# robot_board.net
KiCad netlist of a schematic drawn in EAGLE
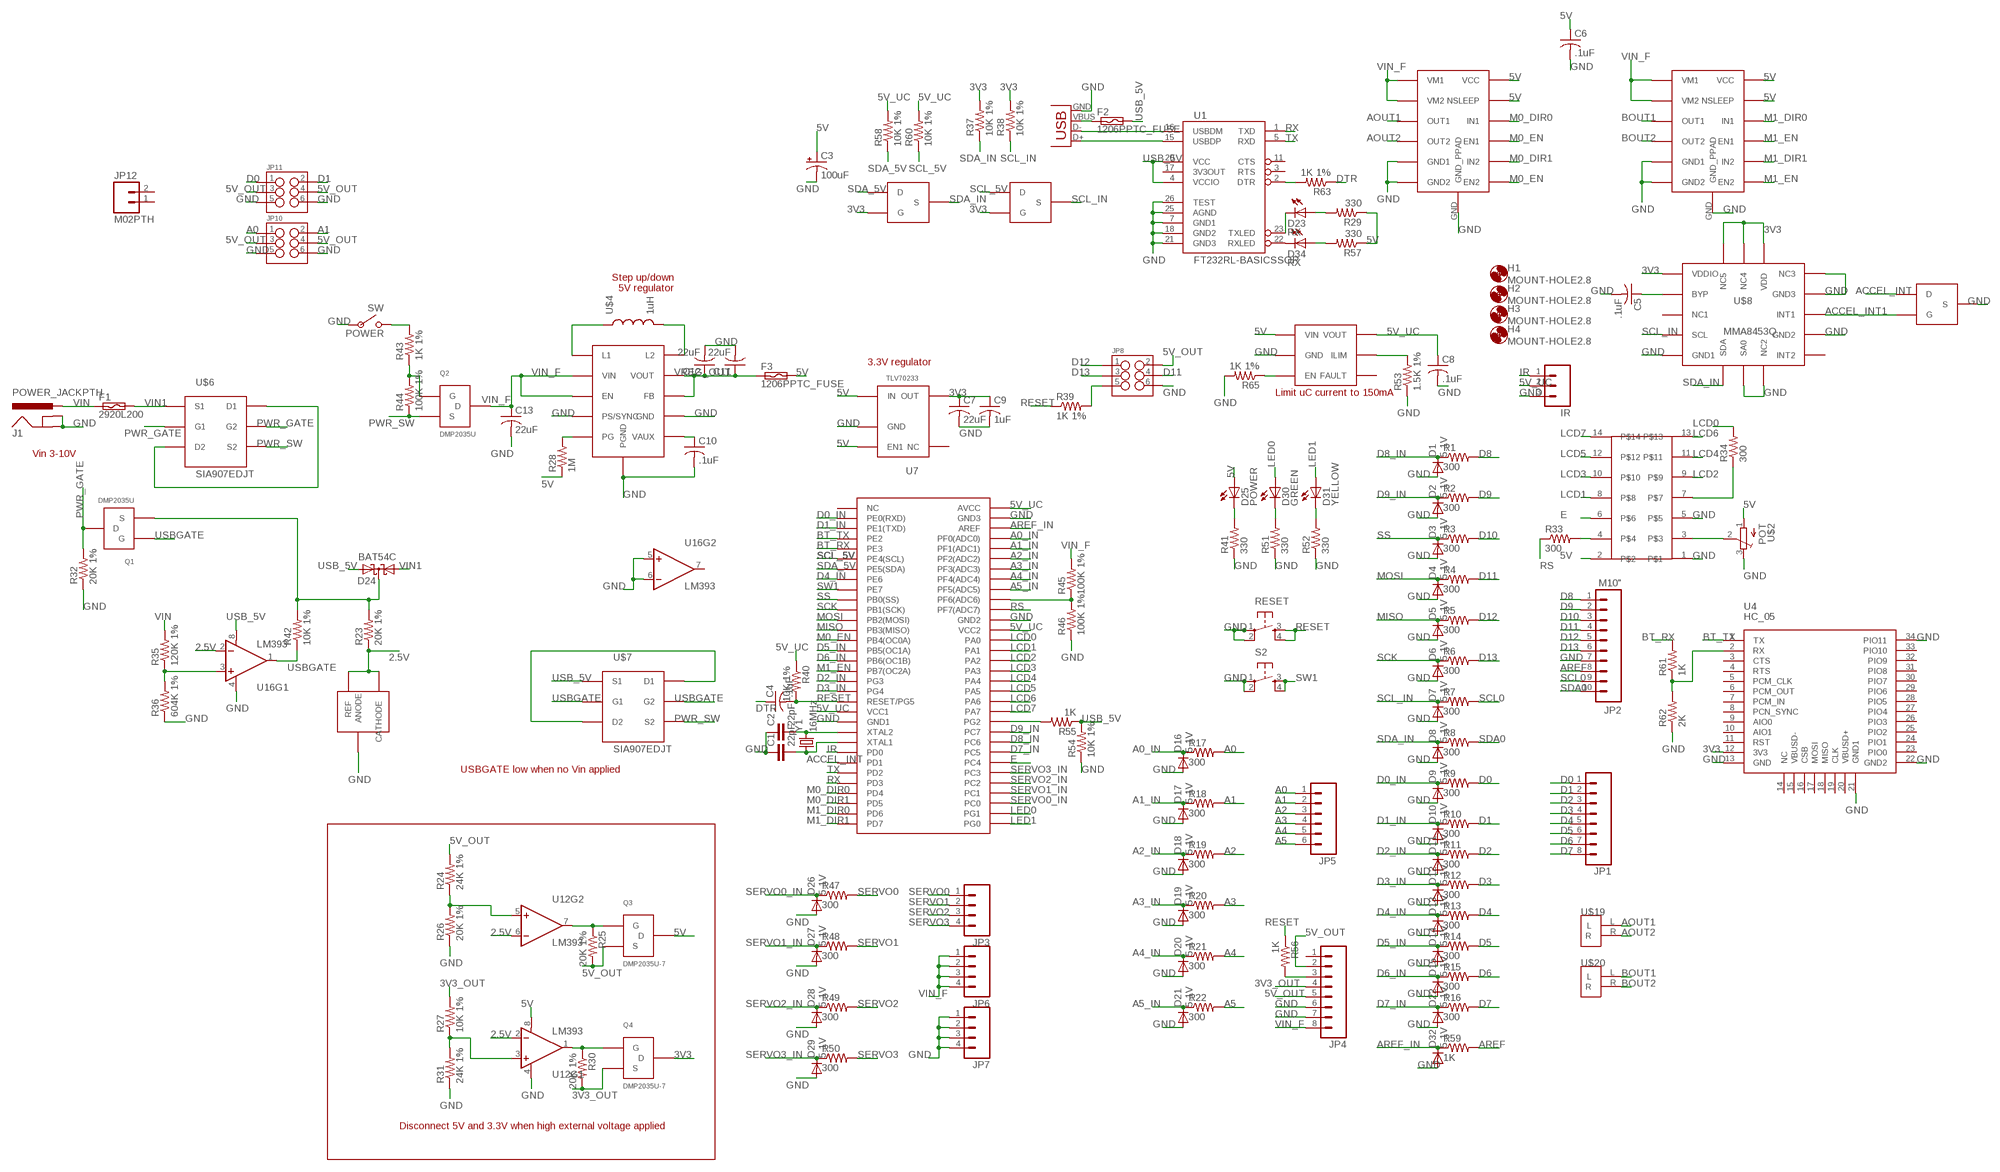
[diagram p0: schematic, sheet 1]

(export (version "E")
  (design (tool "Eeschema 10.0.6"))
  (components
    (comp (ref "C1")
      (value "22pF")
      (footprint "eagle-import:0805")
      (libsource (lib "eagle-import") (part "CAP0805"))
    )
    (comp (ref "C2")
      (value "22pF")
      (footprint "eagle-import:0805")
      (libsource (lib "eagle-import") (part "CAP0805"))
    )
    (comp (ref "C3")
      (value "100uF")
      (footprint "eagle-import:PANASONIC_D")
      (libsource (lib "eagle-import") (part "CAP_POLD"))
    )
    (comp (ref "C4")
      (value ".1uF")
      (footprint "eagle-import:C1206")
      (libsource (lib "eagle-import") (part "C-USC1206"))
    )
    (comp (ref "C5")
      (value ".1uF")
      (footprint "eagle-import:C1206")
      (libsource (lib "eagle-import") (part "C-USC1206"))
    )
    (comp (ref "C6")
      (value ".1uF")
      (footprint "eagle-import:C1206")
      (libsource (lib "eagle-import") (part "C-USC1206"))
    )
    (comp (ref "C7")
      (value "22uF")
      (footprint "eagle-import:C1206")
      (libsource (lib "eagle-import") (part "C-USC1206"))
    )
    (comp (ref "C8")
      (value ".1uF")
      (footprint "eagle-import:C1206")
      (libsource (lib "eagle-import") (part "C-USC1206"))
    )
    (comp (ref "C9")
      (value "1uF")
      (footprint "eagle-import:C1206")
      (libsource (lib "eagle-import") (part "C-USC1206"))
    )
    (comp (ref "C10")
      (value ".1uF")
      (footprint "eagle-import:C1206")
      (libsource (lib "eagle-import") (part "C-USC1206"))
    )
    (comp (ref "C11")
      (value "22uF")
      (footprint "eagle-import:C1206")
      (libsource (lib "eagle-import") (part "C-USC1206"))
    )
    (comp (ref "C12")
      (value "22uF")
      (footprint "eagle-import:C1206")
      (libsource (lib "eagle-import") (part "C-USC1206"))
    )
    (comp (ref "C13")
      (value "22uF")
      (footprint "eagle-import:C1206")
      (libsource (lib "eagle-import") (part "C-USC1206"))
    )
    (comp (ref "D1")
      (value "5.1V")
      (footprint "eagle-import:SOT23-3")
      (libsource (lib "eagle-import") (part "DIODESOT23"))
    )
    (comp (ref "D2")
      (value "5.1V")
      (footprint "eagle-import:SOT23-3")
      (libsource (lib "eagle-import") (part "DIODESOT23"))
    )
    (comp (ref "D3")
      (value "5.1V")
      (footprint "eagle-import:SOT23-3")
      (libsource (lib "eagle-import") (part "DIODESOT23"))
    )
    (comp (ref "D4")
      (value "5.1V")
      (footprint "eagle-import:SOT23-3")
      (libsource (lib "eagle-import") (part "DIODESOT23"))
    )
    (comp (ref "D5")
      (value "5.1V")
      (footprint "eagle-import:SOT23-3")
      (libsource (lib "eagle-import") (part "DIODESOT23"))
    )
    (comp (ref "D6")
      (value "5.1V")
      (footprint "eagle-import:SOT23-3")
      (libsource (lib "eagle-import") (part "DIODESOT23"))
    )
    (comp (ref "D7")
      (value "5.1V")
      (footprint "eagle-import:SOT23-3")
      (libsource (lib "eagle-import") (part "DIODESOT23"))
    )
    (comp (ref "D8")
      (value "5.1V")
      (footprint "eagle-import:SOT23-3")
      (libsource (lib "eagle-import") (part "DIODESOT23"))
    )
    (comp (ref "D9")
      (value "5.1V")
      (footprint "eagle-import:SOT23-3")
      (libsource (lib "eagle-import") (part "DIODESOT23"))
    )
    (comp (ref "D10")
      (value "5.1V")
      (footprint "eagle-import:SOT23-3")
      (libsource (lib "eagle-import") (part "DIODESOT23"))
    )
    (comp (ref "D11")
      (value "5.1V")
      (footprint "eagle-import:SOT23-3")
      (libsource (lib "eagle-import") (part "DIODESOT23"))
    )
    (comp (ref "D12")
      (value "5.1V")
      (footprint "eagle-import:SOT23-3")
      (libsource (lib "eagle-import") (part "DIODESOT23"))
    )
    (comp (ref "D13")
      (value "5.1V")
      (footprint "eagle-import:SOT23-3")
      (libsource (lib "eagle-import") (part "DIODESOT23"))
    )
    (comp (ref "D14")
      (value "5.1V")
      (footprint "eagle-import:SOT23-3")
      (libsource (lib "eagle-import") (part "DIODESOT23"))
    )
    (comp (ref "D15")
      (value "5.1V")
      (footprint "eagle-import:SOT23-3")
      (libsource (lib "eagle-import") (part "DIODESOT23"))
    )
    (comp (ref "D16")
      (value "5.1V")
      (footprint "eagle-import:SOT23-3")
      (libsource (lib "eagle-import") (part "DIODESOT23"))
    )
    (comp (ref "D17")
      (value "5.1V")
      (footprint "eagle-import:SOT23-3")
      (libsource (lib "eagle-import") (part "DIODESOT23"))
    )
    (comp (ref "D18")
      (value "5.1V")
      (footprint "eagle-import:SOT23-3")
      (libsource (lib "eagle-import") (part "DIODESOT23"))
    )
    (comp (ref "D19")
      (value "5.1V")
      (footprint "eagle-import:SOT23-3")
      (libsource (lib "eagle-import") (part "DIODESOT23"))
    )
    (comp (ref "D20")
      (value "5.1V")
      (footprint "eagle-import:SOT23-3")
      (libsource (lib "eagle-import") (part "DIODESOT23"))
    )
    (comp (ref "D21")
      (value "5.1V")
      (footprint "eagle-import:SOT23-3")
      (libsource (lib "eagle-import") (part "DIODESOT23"))
    )
    (comp (ref "D22")
      (value "5.1V")
      (footprint "eagle-import:SOT23-3")
      (libsource (lib "eagle-import") (part "DIODESOT23"))
    )
    (comp (ref "D23")
      (value "RX")
      (footprint "eagle-import:LED-1206")
      (libsource (lib "eagle-import") (part "LED-GREENLILYPAD"))
    )
    (comp (ref "D24")
      (value "BAT54C")
      (footprint "eagle-import:SOT23")
      (libsource (lib "eagle-import") (part "BAT54C"))
    )
    (comp (ref "D25")
      (value "POWER")
      (footprint "eagle-import:LED-1206")
      (libsource (lib "eagle-import") (part "LED-GREENLILYPAD"))
    )
    (comp (ref "D26")
      (value "5.1V")
      (footprint "eagle-import:SOT23-3")
      (libsource (lib "eagle-import") (part "DIODESOT23"))
    )
    (comp (ref "D27")
      (value "5.1V")
      (footprint "eagle-import:SOT23-3")
      (libsource (lib "eagle-import") (part "DIODESOT23"))
    )
    (comp (ref "D28")
      (value "5.1V")
      (footprint "eagle-import:SOT23-3")
      (libsource (lib "eagle-import") (part "DIODESOT23"))
    )
    (comp (ref "D29")
      (value "5.1V")
      (footprint "eagle-import:SOT23-3")
      (libsource (lib "eagle-import") (part "DIODESOT23"))
    )
    (comp (ref "D30")
      (value "GREEN")
      (footprint "eagle-import:LED-1206")
      (libsource (lib "eagle-import") (part "LED-GREENLILYPAD"))
    )
    (comp (ref "D31")
      (value "YELLOW")
      (footprint "eagle-import:LED-1206")
      (libsource (lib "eagle-import") (part "LED-GREENLILYPAD"))
    )
    (comp (ref "D32")
      (value "5.1V")
      (footprint "eagle-import:SOT23-3")
      (libsource (lib "eagle-import") (part "DIODESOT23"))
    )
    (comp (ref "D34")
      (value "RX")
      (footprint "eagle-import:LED-1206")
      (libsource (lib "eagle-import") (part "LED-GREENLILYPAD"))
    )
    (comp (ref "F1")
      (value "2920L200")
      (footprint "eagle-import:SMD050F")
      (libsource (lib "eagle-import") (part "2920L200"))
    )
    (comp (ref "F2")
      (value "1206PPTC_FUSE")
      (footprint "eagle-import:R1206")
      (libsource (lib "eagle-import") (part "1206PPTC_FUSE"))
    )
    (comp (ref "F3")
      (value "1206PPTC_FUSE")
      (footprint "eagle-import:R1206")
      (libsource (lib "eagle-import") (part "1206PPTC_FUSE"))
    )
    (comp (ref "H1")
      (value "MOUNT-HOLE2.8")
      (footprint "eagle-import:2,8")
      (libsource (lib "eagle-import") (part "MOUNT-HOLE2.8"))
    )
    (comp (ref "H2")
      (value "MOUNT-HOLE2.8")
      (footprint "eagle-import:2,8")
      (libsource (lib "eagle-import") (part "MOUNT-HOLE2.8"))
    )
    (comp (ref "H3")
      (value "MOUNT-HOLE2.8")
      (footprint "eagle-import:2,8")
      (libsource (lib "eagle-import") (part "MOUNT-HOLE2.8"))
    )
    (comp (ref "H4")
      (value "MOUNT-HOLE2.8")
      (footprint "eagle-import:2,8")
      (libsource (lib "eagle-import") (part "MOUNT-HOLE2.8"))
    )
    (comp (ref "IR")
      (value "M03PTH")
      (footprint "eagle-import:1X03")
      (libsource (lib "eagle-import") (part "M03PTH"))
    )
    (comp (ref "J1")
      (value "POWER_JACKPTH")
      (footprint "eagle-import:POWER_JACK_PTH")
      (libsource (lib "eagle-import") (part "POWER_JACKPTH"))
    )
    (comp (ref "JP1")
      (value "M081X08")
      (footprint "eagle-import:1X08")
      (libsource (lib "eagle-import") (part "M081X08"))
    )
    (comp (ref "JP2")
      (value "M10\"")
      (footprint "eagle-import:1X10")
      (libsource (lib "eagle-import") (part "M10{dblquote}"))
    )
    (comp (ref "JP3")
      (value "M04PTH")
      (footprint "eagle-import:1X04")
      (libsource (lib "eagle-import") (part "M04PTH"))
    )
    (comp (ref "JP4")
      (value "M081X08")
      (footprint "eagle-import:1X08")
      (libsource (lib "eagle-import") (part "M081X08"))
    )
    (comp (ref "JP5")
      (value "M06SIP")
      (footprint "eagle-import:1X06")
      (libsource (lib "eagle-import") (part "M06SIP"))
    )
    (comp (ref "JP6")
      (value "M04PTH")
      (footprint "eagle-import:1X04")
      (libsource (lib "eagle-import") (part "M04PTH"))
    )
    (comp (ref "JP7")
      (value "M04PTH")
      (footprint "eagle-import:1X04")
      (libsource (lib "eagle-import") (part "M04PTH"))
    )
    (comp (ref "JP8")
      (value "M03X22X3_SILK_SM")
      (footprint "eagle-import:2X3")
      (libsource (lib "eagle-import") (part "M03X22X3_SILK_SM"))
    )
    (comp (ref "JP9")
      (value "USB-B")
      (footprint "eagle-import:USB-B-PTH")
      (libsource (lib "eagle-import") (part "USBPTH"))
    )
    (comp (ref "JP10")
      (value "M03X22X3_SILK_SM")
      (footprint "eagle-import:2X3")
      (libsource (lib "eagle-import") (part "M03X22X3_SILK_SM"))
    )
    (comp (ref "JP11")
      (value "M03X22X3_SILK_SM")
      (footprint "eagle-import:2X3")
      (libsource (lib "eagle-import") (part "M03X22X3_SILK_SM"))
    )
    (comp (ref "JP12")
      (value "M02PTH")
      (footprint "eagle-import:1X02")
      (libsource (lib "eagle-import") (part "M02PTH"))
    )
    (comp (ref "POWER")
      (value "SW")
      (footprint "eagle-import:SW")
      (libsource (lib "eagle-import") (part "SW"))
    )
    (comp (ref "Q1")
      (value "DMP2035U")
      (footprint "eagle-import:SOT23")
      (libsource (lib "eagle-import") (part "DMP2035U"))
    )
    (comp (ref "Q2")
      (value "DMP2035U")
      (footprint "eagle-import:SOT23")
      (libsource (lib "eagle-import") (part "DMP2035U"))
    )
    (comp (ref "Q3")
      (value "DMP2035U-7")
      (footprint "eagle-import:SOT23@1")
      (libsource (lib "eagle-import") (part "DMP2035U-7"))
    )
    (comp (ref "Q4")
      (value "DMP2035U-7")
      (footprint "eagle-import:SOT23@1")
      (libsource (lib "eagle-import") (part "DMP2035U-7"))
    )
    (comp (ref "R1")
      (value "300")
      (footprint "eagle-import:R1206")
      (libsource (lib "eagle-import") (part "R-US_R1206"))
    )
    (comp (ref "R2")
      (value "300")
      (footprint "eagle-import:R1206")
      (libsource (lib "eagle-import") (part "R-US_R1206"))
    )
    (comp (ref "R3")
      (value "300")
      (footprint "eagle-import:R1206")
      (libsource (lib "eagle-import") (part "R-US_R1206"))
    )
    (comp (ref "R4")
      (value "300")
      (footprint "eagle-import:R1206")
      (libsource (lib "eagle-import") (part "R-US_R1206"))
    )
    (comp (ref "R5")
      (value "300")
      (footprint "eagle-import:R1206")
      (libsource (lib "eagle-import") (part "R-US_R1206"))
    )
    (comp (ref "R6")
      (value "300")
      (footprint "eagle-import:R1206")
      (libsource (lib "eagle-import") (part "R-US_R1206"))
    )
    (comp (ref "R7")
      (value "300")
      (footprint "eagle-import:R1206")
      (libsource (lib "eagle-import") (part "R-US_R1206"))
    )
    (comp (ref "R8")
      (value "300")
      (footprint "eagle-import:R1206")
      (libsource (lib "eagle-import") (part "R-US_R1206"))
    )
    (comp (ref "R9")
      (value "300")
      (footprint "eagle-import:R1206")
      (libsource (lib "eagle-import") (part "R-US_R1206"))
    )
    (comp (ref "R10")
      (value "300")
      (footprint "eagle-import:R1206")
      (libsource (lib "eagle-import") (part "R-US_R1206"))
    )
    (comp (ref "R11")
      (value "300")
      (footprint "eagle-import:R1206")
      (libsource (lib "eagle-import") (part "R-US_R1206"))
    )
    (comp (ref "R12")
      (value "300")
      (footprint "eagle-import:R1206")
      (libsource (lib "eagle-import") (part "R-US_R1206"))
    )
    (comp (ref "R13")
      (value "300")
      (footprint "eagle-import:R1206")
      (libsource (lib "eagle-import") (part "R-US_R1206"))
    )
    (comp (ref "R14")
      (value "300")
      (footprint "eagle-import:R1206")
      (libsource (lib "eagle-import") (part "R-US_R1206"))
    )
    (comp (ref "R15")
      (value "300")
      (footprint "eagle-import:R1206")
      (libsource (lib "eagle-import") (part "R-US_R1206"))
    )
    (comp (ref "R16")
      (value "300")
      (footprint "eagle-import:R1206")
      (libsource (lib "eagle-import") (part "R-US_R1206"))
    )
    (comp (ref "R17")
      (value "300")
      (footprint "eagle-import:R1206")
      (libsource (lib "eagle-import") (part "R-US_R1206"))
    )
    (comp (ref "R18")
      (value "300")
      (footprint "eagle-import:R1206")
      (libsource (lib "eagle-import") (part "R-US_R1206"))
    )
    (comp (ref "R19")
      (value "300")
      (footprint "eagle-import:R1206")
      (libsource (lib "eagle-import") (part "R-US_R1206"))
    )
    (comp (ref "R20")
      (value "300")
      (footprint "eagle-import:R1206")
      (libsource (lib "eagle-import") (part "R-US_R1206"))
    )
    (comp (ref "R21")
      (value "300")
      (footprint "eagle-import:R1206")
      (libsource (lib "eagle-import") (part "R-US_R1206"))
    )
    (comp (ref "R22")
      (value "300")
      (footprint "eagle-import:R1206")
      (libsource (lib "eagle-import") (part "R-US_R1206"))
    )
    (comp (ref "R23")
      (value "20K 1%")
      (footprint "eagle-import:R1206")
      (libsource (lib "eagle-import") (part "R-US_R1206"))
    )
    (comp (ref "R24")
      (value "24K 1%")
      (footprint "eagle-import:R1206")
      (libsource (lib "eagle-import") (part "R-US_R1206"))
    )
    (comp (ref "R25")
      (value "20K 1%")
      (footprint "eagle-import:R1206")
      (libsource (lib "eagle-import") (part "R-US_R1206"))
    )
    (comp (ref "R26")
      (value "20K 1%")
      (footprint "eagle-import:R1206")
      (libsource (lib "eagle-import") (part "R-US_R1206"))
    )
    (comp (ref "R27")
      (value "10K 1%")
      (footprint "eagle-import:R1206")
      (libsource (lib "eagle-import") (part "R-US_R1206"))
    )
    (comp (ref "R28")
      (value "1M")
      (footprint "eagle-import:R1206")
      (libsource (lib "eagle-import") (part "R-US_R1206"))
    )
    (comp (ref "R29")
      (value "330")
      (footprint "eagle-import:R1206")
      (libsource (lib "eagle-import") (part "R-US_R1206"))
    )
    (comp (ref "R30")
      (value "20K 1%")
      (footprint "eagle-import:R1206")
      (libsource (lib "eagle-import") (part "R-US_R1206"))
    )
    (comp (ref "R31")
      (value "24K 1%")
      (footprint "eagle-import:R1206")
      (libsource (lib "eagle-import") (part "R-US_R1206"))
    )
    (comp (ref "R32")
      (value "20K 1%")
      (footprint "eagle-import:R1206")
      (libsource (lib "eagle-import") (part "R-US_R1206"))
    )
    (comp (ref "R33")
      (value "300")
      (footprint "eagle-import:R1206")
      (libsource (lib "eagle-import") (part "R-US_R1206"))
    )
    (comp (ref "R34")
      (value "300")
      (footprint "eagle-import:R1206")
      (libsource (lib "eagle-import") (part "R-US_R1206"))
    )
    (comp (ref "R35")
      (value "120K 1%")
      (footprint "eagle-import:R1206")
      (libsource (lib "eagle-import") (part "R-US_R1206"))
    )
    (comp (ref "R36")
      (value "604K 1%")
      (footprint "eagle-import:R1206")
      (libsource (lib "eagle-import") (part "R-US_R1206"))
    )
    (comp (ref "R37")
      (value "10K 1%")
      (footprint "eagle-import:R1206")
      (libsource (lib "eagle-import") (part "R-US_R1206"))
    )
    (comp (ref "R38")
      (value "10K 1%")
      (footprint "eagle-import:R1206")
      (libsource (lib "eagle-import") (part "R-US_R1206"))
    )
    (comp (ref "R39")
      (value "1K 1%")
      (footprint "eagle-import:R1206")
      (libsource (lib "eagle-import") (part "R-US_R1206"))
    )
    (comp (ref "R40")
      (value "10K 1%")
      (footprint "eagle-import:R1206")
      (libsource (lib "eagle-import") (part "R-US_R1206"))
    )
    (comp (ref "R41")
      (value "330")
      (footprint "eagle-import:R1206")
      (libsource (lib "eagle-import") (part "R-US_R1206"))
    )
    (comp (ref "R42")
      (value "10K 1%")
      (footprint "eagle-import:R1206")
      (libsource (lib "eagle-import") (part "R-US_R1206"))
    )
    (comp (ref "R43")
      (value "1K 1%")
      (footprint "eagle-import:R1206")
      (libsource (lib "eagle-import") (part "R-US_R1206"))
    )
    (comp (ref "R44")
      (value "100K 1%")
      (footprint "eagle-import:R1206")
      (libsource (lib "eagle-import") (part "R-US_R1206"))
    )
    (comp (ref "R45")
      (value "100K 1%")
      (footprint "eagle-import:R1206")
      (libsource (lib "eagle-import") (part "R-US_R1206"))
    )
    (comp (ref "R46")
      (value "100K 1%")
      (footprint "eagle-import:R1206")
      (libsource (lib "eagle-import") (part "R-US_R1206"))
    )
    (comp (ref "R47")
      (value "300")
      (footprint "eagle-import:R1206")
      (libsource (lib "eagle-import") (part "R-US_R1206"))
    )
    (comp (ref "R48")
      (value "300")
      (footprint "eagle-import:R1206")
      (libsource (lib "eagle-import") (part "R-US_R1206"))
    )
    (comp (ref "R49")
      (value "300")
      (footprint "eagle-import:R1206")
      (libsource (lib "eagle-import") (part "R-US_R1206"))
    )
    (comp (ref "R50")
      (value "300")
      (footprint "eagle-import:R1206")
      (libsource (lib "eagle-import") (part "R-US_R1206"))
    )
    (comp (ref "R51")
      (value "330")
      (footprint "eagle-import:R1206")
      (libsource (lib "eagle-import") (part "R-US_R1206"))
    )
    (comp (ref "R52")
      (value "330")
      (footprint "eagle-import:R1206")
      (libsource (lib "eagle-import") (part "R-US_R1206"))
    )
    (comp (ref "R53")
      (value "1.5K 1%")
      (footprint "eagle-import:R1206")
      (libsource (lib "eagle-import") (part "R-US_R1206"))
    )
    (comp (ref "R54")
      (value "10K 1%")
      (footprint "eagle-import:R1206")
      (libsource (lib "eagle-import") (part "R-US_R1206"))
    )
    (comp (ref "R55")
      (value "1K")
      (footprint "eagle-import:R1206")
      (libsource (lib "eagle-import") (part "R-US_R1206"))
    )
    (comp (ref "R56")
      (value "1K")
      (footprint "eagle-import:R1206")
      (libsource (lib "eagle-import") (part "R-US_R1206"))
    )
    (comp (ref "R57")
      (value "330")
      (footprint "eagle-import:R1206")
      (libsource (lib "eagle-import") (part "R-US_R1206"))
    )
    (comp (ref "R58")
      (value "10K 1%")
      (footprint "eagle-import:R1206")
      (libsource (lib "eagle-import") (part "R-US_R1206"))
    )
    (comp (ref "R59")
      (value "1K")
      (footprint "eagle-import:R1206")
      (libsource (lib "eagle-import") (part "R-US_R1206"))
    )
    (comp (ref "R60")
      (value "10K 1%")
      (footprint "eagle-import:R1206")
      (libsource (lib "eagle-import") (part "R-US_R1206"))
    )
    (comp (ref "R61")
      (value "1K")
      (footprint "eagle-import:R1206")
      (libsource (lib "eagle-import") (part "R-US_R1206"))
    )
    (comp (ref "R62")
      (value "2K")
      (footprint "eagle-import:R1206")
      (libsource (lib "eagle-import") (part "R-US_R1206"))
    )
    (comp (ref "R63")
      (value "1K 1%")
      (footprint "eagle-import:R1206")
      (libsource (lib "eagle-import") (part "R-US_R1206"))
    )
    (comp (ref "R65")
      (value "1K 1%")
      (footprint "eagle-import:R1206")
      (libsource (lib "eagle-import") (part "R-US_R1206"))
    )
    (comp (ref "RESET")
      (value "TAC_SWITCHPTH")
      (footprint "eagle-import:TACTILE-PTH")
      (libsource (lib "eagle-import") (part "TAC_SWITCHPTH"))
    )
    (comp (ref "S2")
      (value "TAC_SWITCHPTH")
      (footprint "eagle-import:TACTILE-PTH")
      (libsource (lib "eagle-import") (part "TAC_SWITCHPTH"))
    )
    (comp (ref "U$1")
      (value "2X7HEADER")
      (footprint "eagle-import:2X7")
      (libsource (lib "eagle-import") (part "2X7HEADER"))
    )
    (comp (ref "U$2")
      (value "POT")
      (footprint "eagle-import:POT")
      (libsource (lib "eagle-import") (part "POT"))
    )
    (comp (ref "U$3")
      (value "TPS63061")
      (footprint "eagle-import:WSON-10")
      (libsource (lib "eagle-import") (part "TPS63061"))
    )
    (comp (ref "U$4")
      (value "1uH")
      (footprint "eagle-import:TAIYO4012")
      (libsource (lib "eagle-import") (part "TAIYO4012"))
    )
    (comp (ref "U$5")
      (value "AP431SAG-7")
      (footprint "eagle-import:SOT23")
      (libsource (lib "eagle-import") (part "AP431SAG-7"))
    )
    (comp (ref "U$6")
      (value "SIA907EDJT")
      (footprint "eagle-import:SC70T")
      (libsource (lib "eagle-import") (part "SIA907EDJT"))
    )
    (comp (ref "U$7")
      (value "SIA907EDJT")
      (footprint "eagle-import:SC70T")
      (libsource (lib "eagle-import") (part "SIA907EDJT"))
    )
    (comp (ref "U$8")
      (value "MMA8453Q")
      (footprint "eagle-import:QFN-COL")
      (libsource (lib "eagle-import") (part "MMA8453Q"))
    )
    (comp (ref "U$9")
      (value "BSS138")
      (footprint "eagle-import:SOT23")
      (libsource (lib "eagle-import") (part "BSS138"))
    )
    (comp (ref "U$10")
      (value "BSS138")
      (footprint "eagle-import:SOT23")
      (libsource (lib "eagle-import") (part "BSS138"))
    )
    (comp (ref "U$11")
      (value "BSS138")
      (footprint "eagle-import:SOT23")
      (libsource (lib "eagle-import") (part "BSS138"))
    )
    (comp (ref "U$19")
      (value "2POS_TERMINAL")
      (footprint "eagle-import:2POS_TERMINAL")
      (libsource (lib "eagle-import") (part "2POS_TERMINAL"))
    )
    (comp (ref "U$20")
      (value "2POS_TERMINAL")
      (footprint "eagle-import:2POS_TERMINAL")
      (libsource (lib "eagle-import") (part "2POS_TERMINAL"))
    )
    (comp (ref "U1")
      (value "FT232RL-BASICSSOP")
      (footprint "eagle-import:SSOP28DB")
      (libsource (lib "eagle-import") (part "FT232RL-BASICSSOP"))
    )
    (comp (ref "U4")
      (value "HC_05")
      (footprint "eagle-import:BLUETOOTH_SMD")
      (libsource (lib "eagle-import") (part "HC_05"))
    )
    (comp (ref "U7")
      (value "TLV70233")
      (footprint "eagle-import:SOT-23-5")
      (libsource (lib "eagle-import") (part "TLV70233"))
    )
    (comp (ref "U8")
      (value "MIC2009A")
      (footprint "eagle-import:SOT23-M5")
      (libsource (lib "eagle-import") (part "MIC2009A"))
    )
    (comp (ref "U9")
      (value "DRV8839")
      (footprint "eagle-import:PWSON-N12")
      (libsource (lib "eagle-import") (part "DRV8839"))
    )
    (comp (ref "U10")
      (value "DRV8839")
      (footprint "eagle-import:PWSON-N12")
      (libsource (lib "eagle-import") (part "DRV8839"))
    )
    (comp (ref "U12")
      (value "LM393")
      (footprint "eagle-import:SO08")
      (libsource (lib "eagle-import") (part "LM393"))
    )
    (comp (ref "U16")
      (value "LM393")
      (footprint "eagle-import:SO08")
      (libsource (lib "eagle-import") (part "LM393"))
    )
    (comp (ref "U17")
      (value "ATMEGA325PA")
      (footprint "eagle-import:TQFP64")
      (libsource (lib "eagle-import") (part "ATMEGA325PA"))
    )
    (comp (ref "Y1")
      (value "16MHz")
      (footprint "eagle-import:CRYSTAL-SMD-10.5X4.8-2PIN")
      (libsource (lib "eagle-import") (part "CRYSTAL10.5X4.8"))
    )
  )
  (nets
    (net (code "1") (name "/2.5V") (class "Default")
      (node (ref "R23") (pin "1") (pinfunction "1_1") (pintype "passive"))
      (node (ref "U$5") (pin "1") (pinfunction "CATHODE_1") (pintype "bidirectional"))
      (node (ref "U$5") (pin "2") (pinfunction "REF_2") (pintype "bidirectional"))
      (node (ref "U12") (pin "2") (pinfunction "-IN_2") (pintype "input"))
      (node (ref "U12") (pin "6") (pinfunction "-IN_6") (pintype "input"))
      (node (ref "U16") (pin "2") (pinfunction "-IN_2") (pintype "input"))
    )
    (net (code "2") (name "/3V3") (class "Default")
      (node (ref "C7") (pin "1") (pinfunction "1_1") (pintype "passive"))
      (node (ref "C9") (pin "1") (pinfunction "1_1") (pintype "passive"))
      (node (ref "Q4") (pin "3") (pinfunction "D_3") (pintype "bidirectional"))
      (node (ref "R37") (pin "2") (pinfunction "2_2") (pintype "passive"))
      (node (ref "R38") (pin "2") (pinfunction "2_2") (pintype "passive"))
      (node (ref "U$10") (pin "1") (pinfunction "G_1") (pintype "bidirectional"))
      (node (ref "U$8") (pin "P$1") (pinfunction "VDDIO_P$1") (pintype "bidirectional"))
      (node (ref "U$8") (pin "P$14") (pinfunction "VDD_P$14") (pintype "bidirectional"))
      (node (ref "U$8") (pin "P$15") (pinfunction "NC4_P$15") (pintype "bidirectional"))
      (node (ref "U$8") (pin "P$16") (pinfunction "NC5_P$16") (pintype "bidirectional"))
      (node (ref "U$9") (pin "1") (pinfunction "G_1") (pintype "bidirectional"))
      (node (ref "U4") (pin "12") (pinfunction "3V3_12") (pintype "bidirectional"))
      (node (ref "U7") (pin "P$4") (pinfunction "OUT_P$4") (pintype "bidirectional"))
    )
    (net (code "3") (name "/3V3_OUT") (class "Default")
      (node (ref "JP4") (pin "4") (pinfunction "4_4") (pintype "passive"))
      (node (ref "Q4") (pin "2") (pinfunction "S_2") (pintype "bidirectional"))
      (node (ref "R27") (pin "2") (pinfunction "2_2") (pintype "passive"))
      (node (ref "R30") (pin "2") (pinfunction "2_2") (pintype "passive"))
    )
    (net (code "4") (name "/5V") (class "Default")
      (node (ref "C3") (pin "+") (pinfunction "+_+") (pintype "passive"))
      (node (ref "C6") (pin "1") (pinfunction "1_1") (pintype "passive"))
      (node (ref "D25") (pin "A") (pinfunction "A_A") (pintype "passive"))
      (node (ref "F3") (pin "2") (pinfunction "2_2") (pintype "passive"))
      (node (ref "Q3") (pin "3") (pinfunction "D_3") (pintype "bidirectional"))
      (node (ref "R28") (pin "1") (pinfunction "1_1") (pintype "passive"))
      (node (ref "R29") (pin "1") (pinfunction "1_1") (pintype "passive"))
      (node (ref "R57") (pin "1") (pinfunction "1_1") (pintype "passive"))
      (node (ref "U$1") (pin "2") (pinfunction "P$2_2") (pintype "bidirectional"))
      (node (ref "U$2") (pin "1") (pinfunction "A_1") (pintype "passive"))
      (node (ref "U10") (pin "P$7") (pinfunction "VCC_P$7") (pintype "bidirectional"))
      (node (ref "U10") (pin "P$8") (pinfunction "NSLEEP_P$8") (pintype "bidirectional"))
      (node (ref "U12") (pin "8") (pinfunction "V+_8") (pintype "power_in"))
      (node (ref "U7") (pin "P$1") (pinfunction "IN_P$1") (pintype "bidirectional"))
      (node (ref "U7") (pin "P$3") (pinfunction "EN1_P$3") (pintype "bidirectional"))
      (node (ref "U8") (pin "P$1") (pinfunction "VIN_P$1") (pintype "bidirectional"))
      (node (ref "U9") (pin "P$7") (pinfunction "VCC_P$7") (pintype "bidirectional"))
      (node (ref "U9") (pin "P$8") (pinfunction "NSLEEP_P$8") (pintype "bidirectional"))
    )
    (net (code "5") (name "/5V_OUT") (class "Default")
      (node (ref "JP10") (pin "3") (pinfunction "3_3") (pintype "bidirectional"))
      (node (ref "JP10") (pin "4") (pinfunction "4_4") (pintype "bidirectional"))
      (node (ref "JP11") (pin "3") (pinfunction "3_3") (pintype "bidirectional"))
      (node (ref "JP11") (pin "4") (pinfunction "4_4") (pintype "bidirectional"))
      (node (ref "JP4") (pin "2") (pinfunction "2_2") (pintype "passive"))
      (node (ref "JP4") (pin "5") (pinfunction "5_5") (pintype "passive"))
      (node (ref "JP8") (pin "2") (pinfunction "2_2") (pintype "bidirectional"))
      (node (ref "Q3") (pin "2") (pinfunction "S_2") (pintype "bidirectional"))
      (node (ref "R24") (pin "2") (pinfunction "2_2") (pintype "passive"))
      (node (ref "R25") (pin "2") (pinfunction "2_2") (pintype "passive"))
    )
    (net (code "6") (name "/5V_UC") (class "Default")
      (node (ref "C8") (pin "1") (pinfunction "1_1") (pintype "passive"))
      (node (ref "IR") (pin "2") (pinfunction "2_2") (pintype "passive"))
      (node (ref "R40") (pin "1") (pinfunction "1_1") (pintype "passive"))
      (node (ref "R58") (pin "2") (pinfunction "2_2") (pintype "passive"))
      (node (ref "R60") (pin "2") (pinfunction "2_2") (pintype "passive"))
      (node (ref "U17") (pin "21") (pinfunction "VCC1_21") (pintype "bidirectional"))
      (node (ref "U17") (pin "52") (pinfunction "VCC2_52") (pintype "bidirectional"))
      (node (ref "U17") (pin "64") (pinfunction "AVCC_64") (pintype "bidirectional"))
      (node (ref "U8") (pin "P$6") (pinfunction "VOUT_P$6") (pintype "bidirectional"))
    )
    (net (code "7") (name "/A0") (class "Default")
      (node (ref "JP10") (pin "1") (pinfunction "1_1") (pintype "bidirectional"))
      (node (ref "JP5") (pin "1") (pinfunction "1_1") (pintype "passive"))
      (node (ref "R17") (pin "2") (pinfunction "2_2") (pintype "passive"))
    )
    (net (code "8") (name "/A0_IN") (class "Default")
      (node (ref "D16") (pin "3") (pinfunction "C_3") (pintype "passive"))
      (node (ref "R17") (pin "1") (pinfunction "1_1") (pintype "passive"))
      (node (ref "U17") (pin "61") (pinfunction "PF0(ADC0)_61") (pintype "bidirectional"))
    )
    (net (code "9") (name "/A1") (class "Default")
      (node (ref "JP10") (pin "2") (pinfunction "2_2") (pintype "bidirectional"))
      (node (ref "JP5") (pin "2") (pinfunction "2_2") (pintype "passive"))
      (node (ref "R18") (pin "2") (pinfunction "2_2") (pintype "passive"))
    )
    (net (code "10") (name "/A1_IN") (class "Default")
      (node (ref "D17") (pin "3") (pinfunction "C_3") (pintype "passive"))
      (node (ref "R18") (pin "1") (pinfunction "1_1") (pintype "passive"))
      (node (ref "U17") (pin "60") (pinfunction "PF1(ADC1)_60") (pintype "bidirectional"))
    )
    (net (code "11") (name "/A2") (class "Default")
      (node (ref "JP5") (pin "3") (pinfunction "3_3") (pintype "passive"))
      (node (ref "R19") (pin "2") (pinfunction "2_2") (pintype "passive"))
    )
    (net (code "12") (name "/A2_IN") (class "Default")
      (node (ref "D18") (pin "3") (pinfunction "C_3") (pintype "passive"))
      (node (ref "R19") (pin "1") (pinfunction "1_1") (pintype "passive"))
      (node (ref "U17") (pin "59") (pinfunction "PF2(ADC2)_59") (pintype "bidirectional"))
    )
    (net (code "13") (name "/A3") (class "Default")
      (node (ref "JP5") (pin "4") (pinfunction "4_4") (pintype "passive"))
      (node (ref "R20") (pin "2") (pinfunction "2_2") (pintype "passive"))
    )
    (net (code "14") (name "/A3_IN") (class "Default")
      (node (ref "D19") (pin "3") (pinfunction "C_3") (pintype "passive"))
      (node (ref "R20") (pin "1") (pinfunction "1_1") (pintype "passive"))
      (node (ref "U17") (pin "58") (pinfunction "PF3(ADC3)_58") (pintype "bidirectional"))
    )
    (net (code "15") (name "/A4") (class "Default")
      (node (ref "JP5") (pin "5") (pinfunction "5_5") (pintype "passive"))
      (node (ref "R21") (pin "2") (pinfunction "2_2") (pintype "passive"))
    )
    (net (code "16") (name "/A4_IN") (class "Default")
      (node (ref "D20") (pin "3") (pinfunction "C_3") (pintype "passive"))
      (node (ref "R21") (pin "1") (pinfunction "1_1") (pintype "passive"))
      (node (ref "U17") (pin "57") (pinfunction "PF4(ADC4)_57") (pintype "bidirectional"))
    )
    (net (code "17") (name "/A5") (class "Default")
      (node (ref "JP5") (pin "6") (pinfunction "6_6") (pintype "passive"))
      (node (ref "R22") (pin "2") (pinfunction "2_2") (pintype "passive"))
    )
    (net (code "18") (name "/A5_IN") (class "Default")
      (node (ref "D21") (pin "3") (pinfunction "C_3") (pintype "passive"))
      (node (ref "R22") (pin "1") (pinfunction "1_1") (pintype "passive"))
      (node (ref "U17") (pin "56") (pinfunction "PF5(ADC5)_56") (pintype "bidirectional"))
    )
    (net (code "19") (name "/ACCEL_INT") (class "Default")
      (node (ref "U$11") (pin "3") (pinfunction "D_3") (pintype "bidirectional"))
      (node (ref "U17") (pin "26") (pinfunction "PD1_26") (pintype "bidirectional"))
    )
    (net (code "20") (name "/ACCEL_INT1") (class "Default")
      (node (ref "U$11") (pin "1") (pinfunction "G_1") (pintype "bidirectional"))
      (node (ref "U$8") (pin "P$11") (pinfunction "INT1_P$11") (pintype "bidirectional"))
    )
    (net (code "21") (name "/AOUT1") (class "Default")
      (node (ref "U$19") (pin "L") (pinfunction "L_L") (pintype "bidirectional"))
      (node (ref "U9") (pin "P$3") (pinfunction "OUT1_P$3") (pintype "bidirectional"))
    )
    (net (code "22") (name "/AOUT2") (class "Default")
      (node (ref "U$19") (pin "R") (pinfunction "R_R") (pintype "bidirectional"))
      (node (ref "U9") (pin "P$4") (pinfunction "OUT2_P$4") (pintype "bidirectional"))
    )
    (net (code "23") (name "/AREF") (class "Default")
      (node (ref "JP2") (pin "8") (pinfunction "8_8") (pintype "passive"))
      (node (ref "R59") (pin "2") (pinfunction "2_2") (pintype "passive"))
    )
    (net (code "24") (name "/AREF_IN") (class "Default")
      (node (ref "D32") (pin "3") (pinfunction "C_3") (pintype "passive"))
      (node (ref "R59") (pin "1") (pinfunction "1_1") (pintype "passive"))
      (node (ref "U17") (pin "62") (pinfunction "AREF_62") (pintype "bidirectional"))
    )
    (net (code "25") (name "/BOUT1") (class "Default")
      (node (ref "U$20") (pin "L") (pinfunction "L_L") (pintype "bidirectional"))
      (node (ref "U10") (pin "P$3") (pinfunction "OUT1_P$3") (pintype "bidirectional"))
    )
    (net (code "26") (name "/BOUT2") (class "Default")
      (node (ref "U$20") (pin "R") (pinfunction "R_R") (pintype "bidirectional"))
      (node (ref "U10") (pin "P$4") (pinfunction "OUT2_P$4") (pintype "bidirectional"))
    )
    (net (code "27") (name "/BT_RX") (class "Default")
      (node (ref "R61") (pin "2") (pinfunction "2_2") (pintype "passive"))
      (node (ref "U17") (pin "5") (pinfunction "PE3_5") (pintype "bidirectional"))
    )
    (net (code "28") (name "/BT_TX") (class "Default")
      (node (ref "U17") (pin "4") (pinfunction "PE2_4") (pintype "bidirectional"))
      (node (ref "U4") (pin "1") (pinfunction "TX_1") (pintype "bidirectional"))
    )
    (net (code "29") (name "/D0") (class "Default")
      (node (ref "JP1") (pin "1") (pinfunction "1_1") (pintype "passive"))
      (node (ref "JP11") (pin "1") (pinfunction "1_1") (pintype "bidirectional"))
      (node (ref "R9") (pin "2") (pinfunction "2_2") (pintype "passive"))
    )
    (net (code "30") (name "/D0_IN") (class "Default")
      (node (ref "D9") (pin "3") (pinfunction "C_3") (pintype "passive"))
      (node (ref "R9") (pin "1") (pinfunction "1_1") (pintype "passive"))
      (node (ref "U17") (pin "2") (pinfunction "PE0(RXD)_2") (pintype "bidirectional"))
    )
    (net (code "31") (name "/D1") (class "Default")
      (node (ref "JP1") (pin "2") (pinfunction "2_2") (pintype "passive"))
      (node (ref "JP11") (pin "2") (pinfunction "2_2") (pintype "bidirectional"))
      (node (ref "R10") (pin "2") (pinfunction "2_2") (pintype "passive"))
    )
    (net (code "32") (name "/D1_IN") (class "Default")
      (node (ref "D10") (pin "3") (pinfunction "C_3") (pintype "passive"))
      (node (ref "R10") (pin "1") (pinfunction "1_1") (pintype "passive"))
      (node (ref "U17") (pin "3") (pinfunction "PE1(TXD)_3") (pintype "bidirectional"))
    )
    (net (code "33") (name "/D2") (class "Default")
      (node (ref "JP1") (pin "3") (pinfunction "3_3") (pintype "passive"))
      (node (ref "R11") (pin "2") (pinfunction "2_2") (pintype "passive"))
    )
    (net (code "34") (name "/D2_IN") (class "Default")
      (node (ref "D11") (pin "3") (pinfunction "C_3") (pintype "passive"))
      (node (ref "R11") (pin "1") (pinfunction "1_1") (pintype "passive"))
      (node (ref "U17") (pin "18") (pinfunction "PG3_18") (pintype "bidirectional"))
    )
    (net (code "35") (name "/D3") (class "Default")
      (node (ref "JP1") (pin "4") (pinfunction "4_4") (pintype "passive"))
      (node (ref "R12") (pin "2") (pinfunction "2_2") (pintype "passive"))
    )
    (net (code "36") (name "/D3_IN") (class "Default")
      (node (ref "D12") (pin "3") (pinfunction "C_3") (pintype "passive"))
      (node (ref "R12") (pin "1") (pinfunction "1_1") (pintype "passive"))
      (node (ref "U17") (pin "19") (pinfunction "PG4_19") (pintype "bidirectional"))
    )
    (net (code "37") (name "/D4") (class "Default")
      (node (ref "JP1") (pin "5") (pinfunction "5_5") (pintype "passive"))
      (node (ref "R13") (pin "2") (pinfunction "2_2") (pintype "passive"))
    )
    (net (code "38") (name "/D4_IN") (class "Default")
      (node (ref "D13") (pin "3") (pinfunction "C_3") (pintype "passive"))
      (node (ref "R13") (pin "1") (pinfunction "1_1") (pintype "passive"))
      (node (ref "U17") (pin "8") (pinfunction "PE6_8") (pintype "bidirectional"))
    )
    (net (code "39") (name "/D5") (class "Default")
      (node (ref "JP1") (pin "6") (pinfunction "6_6") (pintype "passive"))
      (node (ref "R14") (pin "2") (pinfunction "2_2") (pintype "passive"))
    )
    (net (code "40") (name "/D5_IN") (class "Default")
      (node (ref "D14") (pin "3") (pinfunction "C_3") (pintype "passive"))
      (node (ref "R14") (pin "1") (pinfunction "1_1") (pintype "passive"))
      (node (ref "U17") (pin "15") (pinfunction "PB5(OC1A)_15") (pintype "bidirectional"))
    )
    (net (code "41") (name "/D6") (class "Default")
      (node (ref "JP1") (pin "7") (pinfunction "7_7") (pintype "passive"))
      (node (ref "R15") (pin "2") (pinfunction "2_2") (pintype "passive"))
    )
    (net (code "42") (name "/D6_IN") (class "Default")
      (node (ref "D15") (pin "3") (pinfunction "C_3") (pintype "passive"))
      (node (ref "R15") (pin "1") (pinfunction "1_1") (pintype "passive"))
      (node (ref "U17") (pin "16") (pinfunction "PB6(OC1B)_16") (pintype "bidirectional"))
    )
    (net (code "43") (name "/D7") (class "Default")
      (node (ref "JP1") (pin "8") (pinfunction "8_8") (pintype "passive"))
      (node (ref "R16") (pin "2") (pinfunction "2_2") (pintype "passive"))
    )
    (net (code "44") (name "/D7_IN") (class "Default")
      (node (ref "D22") (pin "3") (pinfunction "C_3") (pintype "passive"))
      (node (ref "R16") (pin "1") (pinfunction "1_1") (pintype "passive"))
      (node (ref "U17") (pin "40") (pinfunction "PC5_40") (pintype "bidirectional"))
    )
    (net (code "45") (name "/D8") (class "Default")
      (node (ref "JP2") (pin "1") (pinfunction "1_1") (pintype "passive"))
      (node (ref "R1") (pin "2") (pinfunction "2_2") (pintype "passive"))
    )
    (net (code "46") (name "/D8_IN") (class "Default")
      (node (ref "D1") (pin "3") (pinfunction "C_3") (pintype "passive"))
      (node (ref "R1") (pin "1") (pinfunction "1_1") (pintype "passive"))
      (node (ref "U17") (pin "41") (pinfunction "PC6_41") (pintype "bidirectional"))
    )
    (net (code "47") (name "/D9") (class "Default")
      (node (ref "JP2") (pin "2") (pinfunction "2_2") (pintype "passive"))
      (node (ref "R2") (pin "2") (pinfunction "2_2") (pintype "passive"))
    )
    (net (code "48") (name "/D9_IN") (class "Default")
      (node (ref "D2") (pin "3") (pinfunction "C_3") (pintype "passive"))
      (node (ref "R2") (pin "1") (pinfunction "1_1") (pintype "passive"))
      (node (ref "U17") (pin "42") (pinfunction "PC7_42") (pintype "bidirectional"))
    )
    (net (code "49") (name "/D10") (class "Default")
      (node (ref "JP2") (pin "3") (pinfunction "3_3") (pintype "passive"))
      (node (ref "R3") (pin "2") (pinfunction "2_2") (pintype "passive"))
    )
    (net (code "50") (name "/D11") (class "Default")
      (node (ref "JP2") (pin "4") (pinfunction "4_4") (pintype "passive"))
      (node (ref "JP8") (pin "4") (pinfunction "4_4") (pintype "bidirectional"))
      (node (ref "R4") (pin "2") (pinfunction "2_2") (pintype "passive"))
    )
    (net (code "51") (name "/D12") (class "Default")
      (node (ref "JP2") (pin "5") (pinfunction "5_5") (pintype "passive"))
      (node (ref "JP8") (pin "1") (pinfunction "1_1") (pintype "bidirectional"))
      (node (ref "R5") (pin "2") (pinfunction "2_2") (pintype "passive"))
    )
    (net (code "52") (name "/D13") (class "Default")
      (node (ref "JP2") (pin "6") (pinfunction "6_6") (pintype "passive"))
      (node (ref "JP8") (pin "3") (pinfunction "3_3") (pintype "bidirectional"))
      (node (ref "R6") (pin "2") (pinfunction "2_2") (pintype "passive"))
    )
    (net (code "53") (name "/DTR") (class "Default")
      (node (ref "C4") (pin "1") (pinfunction "1_1") (pintype "passive"))
      (node (ref "R63") (pin "1") (pinfunction "1_1") (pintype "passive"))
    )
    (net (code "54") (name "/E") (class "Default")
      (node (ref "U$1") (pin "6") (pinfunction "P$6_6") (pintype "bidirectional"))
      (node (ref "U17") (pin "39") (pinfunction "PC4_39") (pintype "bidirectional"))
    )
    (net (code "55") (name "/GND") (class "Default")
      (node (ref "C1") (pin "1") (pinfunction "1_1") (pintype "passive"))
      (node (ref "C10") (pin "2") (pinfunction "2_2") (pintype "passive"))
      (node (ref "C11") (pin "2") (pinfunction "2_2") (pintype "passive"))
      (node (ref "C12") (pin "2") (pinfunction "2_2") (pintype "passive"))
      (node (ref "C13") (pin "2") (pinfunction "2_2") (pintype "passive"))
      (node (ref "C2") (pin "1") (pinfunction "1_1") (pintype "passive"))
      (node (ref "C3") (pin "-") (pinfunction "-_-") (pintype "passive"))
      (node (ref "C5") (pin "2") (pinfunction "2_2") (pintype "passive"))
      (node (ref "C6") (pin "2") (pinfunction "2_2") (pintype "passive"))
      (node (ref "C7") (pin "2") (pinfunction "2_2") (pintype "passive"))
      (node (ref "C8") (pin "2") (pinfunction "2_2") (pintype "passive"))
      (node (ref "C9") (pin "2") (pinfunction "2_2") (pintype "passive"))
      (node (ref "D1") (pin "1") (pinfunction "A_1") (pintype "passive"))
      (node (ref "D10") (pin "1") (pinfunction "A_1") (pintype "passive"))
      (node (ref "D11") (pin "1") (pinfunction "A_1") (pintype "passive"))
      (node (ref "D12") (pin "1") (pinfunction "A_1") (pintype "passive"))
      (node (ref "D13") (pin "1") (pinfunction "A_1") (pintype "passive"))
      (node (ref "D14") (pin "1") (pinfunction "A_1") (pintype "passive"))
      (node (ref "D15") (pin "1") (pinfunction "A_1") (pintype "passive"))
      (node (ref "D16") (pin "1") (pinfunction "A_1") (pintype "passive"))
      (node (ref "D17") (pin "1") (pinfunction "A_1") (pintype "passive"))
      (node (ref "D18") (pin "1") (pinfunction "A_1") (pintype "passive"))
      (node (ref "D19") (pin "1") (pinfunction "A_1") (pintype "passive"))
      (node (ref "D2") (pin "1") (pinfunction "A_1") (pintype "passive"))
      (node (ref "D20") (pin "1") (pinfunction "A_1") (pintype "passive"))
      (node (ref "D21") (pin "1") (pinfunction "A_1") (pintype "passive"))
      (node (ref "D22") (pin "1") (pinfunction "A_1") (pintype "passive"))
      (node (ref "D26") (pin "1") (pinfunction "A_1") (pintype "passive"))
      (node (ref "D27") (pin "1") (pinfunction "A_1") (pintype "passive"))
      (node (ref "D28") (pin "1") (pinfunction "A_1") (pintype "passive"))
      (node (ref "D29") (pin "1") (pinfunction "A_1") (pintype "passive"))
      (node (ref "D3") (pin "1") (pinfunction "A_1") (pintype "passive"))
      (node (ref "D32") (pin "1") (pinfunction "A_1") (pintype "passive"))
      (node (ref "D4") (pin "1") (pinfunction "A_1") (pintype "passive"))
      (node (ref "D5") (pin "1") (pinfunction "A_1") (pintype "passive"))
      (node (ref "D6") (pin "1") (pinfunction "A_1") (pintype "passive"))
      (node (ref "D7") (pin "1") (pinfunction "A_1") (pintype "passive"))
      (node (ref "D8") (pin "1") (pinfunction "A_1") (pintype "passive"))
      (node (ref "D9") (pin "1") (pinfunction "A_1") (pintype "passive"))
      (node (ref "IR") (pin "3") (pinfunction "3_3") (pintype "passive"))
      (node (ref "J1") (pin "GND") (pinfunction "GND_GND") (pintype "bidirectional"))
      (node (ref "J1") (pin "GNDBREAK") (pinfunction "GNDBREAK_GNDBREAK") (pintype "bidirectional"))
      (node (ref "JP10") (pin "5") (pinfunction "5_5") (pintype "bidirectional"))
      (node (ref "JP10") (pin "6") (pinfunction "6_6") (pintype "bidirectional"))
      (node (ref "JP11") (pin "5") (pinfunction "5_5") (pintype "bidirectional"))
      (node (ref "JP11") (pin "6") (pinfunction "6_6") (pintype "bidirectional"))
      (node (ref "JP2") (pin "7") (pinfunction "7_7") (pintype "passive"))
      (node (ref "JP4") (pin "6") (pinfunction "6_6") (pintype "passive"))
      (node (ref "JP4") (pin "7") (pinfunction "7_7") (pintype "passive"))
      (node (ref "JP7") (pin "1") (pinfunction "1_1") (pintype "passive"))
      (node (ref "JP7") (pin "2") (pinfunction "2_2") (pintype "passive"))
      (node (ref "JP7") (pin "3") (pinfunction "3_3") (pintype "passive"))
      (node (ref "JP7") (pin "4") (pinfunction "4_4") (pintype "passive"))
      (node (ref "JP8") (pin "6") (pinfunction "6_6") (pintype "bidirectional"))
      (node (ref "JP9") (pin "GND") (pinfunction "GND_GND") (pintype "bidirectional"))
      (node (ref "POWER") (pin "P$2") (pinfunction "P$2_P$2") (pintype "bidirectional"))
      (node (ref "R26") (pin "1") (pinfunction "1_1") (pintype "passive"))
      (node (ref "R31") (pin "1") (pinfunction "1_1") (pintype "passive"))
      (node (ref "R32") (pin "1") (pinfunction "1_1") (pintype "passive"))
      (node (ref "R36") (pin "1") (pinfunction "1_1") (pintype "passive"))
      (node (ref "R41") (pin "1") (pinfunction "1_1") (pintype "passive"))
      (node (ref "R46") (pin "1") (pinfunction "1_1") (pintype "passive"))
      (node (ref "R51") (pin "1") (pinfunction "1_1") (pintype "passive"))
      (node (ref "R52") (pin "1") (pinfunction "1_1") (pintype "passive"))
      (node (ref "R53") (pin "1") (pinfunction "1_1") (pintype "passive"))
      (node (ref "R54") (pin "1") (pinfunction "1_1") (pintype "passive"))
      (node (ref "R62") (pin "1") (pinfunction "1_1") (pintype "passive"))
      (node (ref "R65") (pin "2") (pinfunction "2_2") (pintype "passive"))
      (node (ref "RESET") (pin "1") (pinfunction "1_1") (pintype "passive"))
      (node (ref "RESET") (pin "2") (pinfunction "2_2") (pintype "passive"))
      (node (ref "S2") (pin "1") (pinfunction "1_1") (pintype "passive"))
      (node (ref "S2") (pin "2") (pinfunction "2_2") (pintype "passive"))
      (node (ref "U$1") (pin "1") (pinfunction "P$1_1") (pintype "bidirectional"))
      (node (ref "U$1") (pin "5") (pinfunction "P$5_5") (pintype "bidirectional"))
      (node (ref "U$11") (pin "2") (pinfunction "S_2") (pintype "bidirectional"))
      (node (ref "U$2") (pin "3") (pinfunction "E_3") (pintype "passive"))
      (node (ref "U$3") (pin "GND@N1") (pinfunction "PGND_GND@N1") (pintype "bidirectional"))
      (node (ref "U$3") (pin "GND@N2") (pinfunction "PGND_GND@N2") (pintype "bidirectional"))
      (node (ref "U$3") (pin "GND@N3") (pinfunction "PGND_GND@N3") (pintype "bidirectional"))
      (node (ref "U$3") (pin "GND@N4") (pinfunction "PGND_GND@N4") (pintype "bidirectional"))
      (node (ref "U$3") (pin "GND@N5") (pinfunction "PGND_GND@N5") (pintype "bidirectional"))
      (node (ref "U$3") (pin "GND@N6") (pinfunction "PGND_GND@N6") (pintype "bidirectional"))
      (node (ref "U$3") (pin "GND@N7") (pinfunction "PGND_GND@N7") (pintype "bidirectional"))
      (node (ref "U$3") (pin "GND@N8") (pinfunction "PGND_GND@N8") (pintype "bidirectional"))
      (node (ref "U$3") (pin "P$11") (pinfunction "PGND_P$11") (pintype "bidirectional"))
      (node (ref "U$3") (pin "P$4") (pinfunction "PS/SYNC_P$4") (pintype "bidirectional"))
      (node (ref "U$3") (pin "P$7") (pinfunction "GND_P$7") (pintype "bidirectional"))
      (node (ref "U$5") (pin "3") (pinfunction "ANODE_3") (pintype "bidirectional"))
      (node (ref "U$8") (pin "P$10") (pinfunction "GND2_P$10") (pintype "bidirectional"))
      (node (ref "U$8") (pin "P$12") (pinfunction "GND3_P$12") (pintype "bidirectional"))
      (node (ref "U$8") (pin "P$13") (pinfunction "NC3_P$13") (pintype "bidirectional"))
      (node (ref "U$8") (pin "P$5") (pinfunction "GND1_P$5") (pintype "bidirectional"))
      (node (ref "U$8") (pin "P$7") (pinfunction "SA0_P$7") (pintype "bidirectional"))
      (node (ref "U$8") (pin "P$8") (pinfunction "NC2_P$8") (pintype "bidirectional"))
      (node (ref "U1") (pin "18") (pinfunction "GND2_18") (pintype "power_in"))
      (node (ref "U1") (pin "21") (pinfunction "GND3_21") (pintype "power_in"))
      (node (ref "U1") (pin "25") (pinfunction "AGND_25") (pintype "power_in"))
      (node (ref "U1") (pin "26") (pinfunction "TEST_26") (pintype "input"))
      (node (ref "U1") (pin "7") (pinfunction "GND1_7") (pintype "power_in"))
      (node (ref "U10") (pin "GND") (pinfunction "GND_PPAD_GND") (pintype "bidirectional"))
      (node (ref "U10") (pin "P$5") (pinfunction "GND1_P$5") (pintype "bidirectional"))
      (node (ref "U10") (pin "P$6") (pinfunction "GND2_P$6") (pintype "bidirectional"))
      (node (ref "U12") (pin "4") (pinfunction "V-_4") (pintype "power_in"))
      (node (ref "U16") (pin "4") (pinfunction "V-_4") (pintype "power_in"))
      (node (ref "U16") (pin "5") (pinfunction "+IN_5") (pintype "input"))
      (node (ref "U16") (pin "6") (pinfunction "-IN_6") (pintype "input"))
      (node (ref "U17") (pin "22") (pinfunction "GND1_22") (pintype "bidirectional"))
      (node (ref "U17") (pin "53") (pinfunction "GND2_53") (pintype "bidirectional"))
      (node (ref "U17") (pin "63") (pinfunction "GND3_63") (pintype "bidirectional"))
      (node (ref "U4") (pin "13") (pinfunction "GND_13") (pintype "bidirectional"))
      (node (ref "U4") (pin "21") (pinfunction "GND1_21") (pintype "bidirectional"))
      (node (ref "U4") (pin "22") (pinfunction "GND2_22") (pintype "bidirectional"))
      (node (ref "U4") (pin "34") (pinfunction "PIO11_34") (pintype "bidirectional"))
      (node (ref "U7") (pin "P$2") (pinfunction "GND_P$2") (pintype "bidirectional"))
      (node (ref "U8") (pin "P$2") (pinfunction "GND_P$2") (pintype "bidirectional"))
      (node (ref "U9") (pin "GND") (pinfunction "GND_PPAD_GND") (pintype "bidirectional"))
      (node (ref "U9") (pin "P$5") (pinfunction "GND1_P$5") (pintype "bidirectional"))
      (node (ref "U9") (pin "P$6") (pinfunction "GND2_P$6") (pintype "bidirectional"))
    )
    (net (code "56") (name "/IR") (class "Default")
      (node (ref "IR") (pin "1") (pinfunction "1_1") (pintype "passive"))
      (node (ref "U17") (pin "25") (pinfunction "PD0_25") (pintype "bidirectional"))
    )
    (net (code "57") (name "/LCD0") (class "Default")
      (node (ref "R34") (pin "2") (pinfunction "2_2") (pintype "passive"))
      (node (ref "U17") (pin "51") (pinfunction "PA0_51") (pintype "bidirectional"))
    )
    (net (code "58") (name "/LCD1") (class "Default")
      (node (ref "U$1") (pin "8") (pinfunction "P$8_8") (pintype "bidirectional"))
      (node (ref "U17") (pin "50") (pinfunction "PA1_50") (pintype "bidirectional"))
    )
    (net (code "59") (name "/LCD2") (class "Default")
      (node (ref "U$1") (pin "9") (pinfunction "P$9_9") (pintype "bidirectional"))
      (node (ref "U17") (pin "49") (pinfunction "PA2_49") (pintype "bidirectional"))
    )
    (net (code "60") (name "/LCD3") (class "Default")
      (node (ref "U$1") (pin "10") (pinfunction "P$10_10") (pintype "bidirectional"))
      (node (ref "U17") (pin "48") (pinfunction "PA3_48") (pintype "bidirectional"))
    )
    (net (code "61") (name "/LCD4") (class "Default")
      (node (ref "U$1") (pin "11") (pinfunction "P$11_11") (pintype "bidirectional"))
      (node (ref "U17") (pin "47") (pinfunction "PA4_47") (pintype "bidirectional"))
    )
    (net (code "62") (name "/LCD5") (class "Default")
      (node (ref "U$1") (pin "12") (pinfunction "P$12_12") (pintype "bidirectional"))
      (node (ref "U17") (pin "46") (pinfunction "PA5_46") (pintype "bidirectional"))
    )
    (net (code "63") (name "/LCD6") (class "Default")
      (node (ref "U$1") (pin "13") (pinfunction "P$13_13") (pintype "bidirectional"))
      (node (ref "U17") (pin "45") (pinfunction "PA6_45") (pintype "bidirectional"))
    )
    (net (code "64") (name "/LCD7") (class "Default")
      (node (ref "U$1") (pin "14") (pinfunction "P$14_14") (pintype "bidirectional"))
      (node (ref "U17") (pin "44") (pinfunction "PA7_44") (pintype "bidirectional"))
    )
    (net (code "65") (name "/LED0") (class "Default")
      (node (ref "D30") (pin "A") (pinfunction "A_A") (pintype "passive"))
      (node (ref "U17") (pin "34") (pinfunction "PG1_34") (pintype "bidirectional"))
    )
    (net (code "66") (name "/LED1") (class "Default")
      (node (ref "D31") (pin "A") (pinfunction "A_A") (pintype "passive"))
      (node (ref "U17") (pin "33") (pinfunction "PG0_33") (pintype "bidirectional"))
    )
    (net (code "67") (name "/M0_DIR0") (class "Default")
      (node (ref "U17") (pin "29") (pinfunction "PD4_29") (pintype "bidirectional"))
      (node (ref "U9") (pin "P$9") (pinfunction "IN1_P$9") (pintype "bidirectional"))
    )
    (net (code "68") (name "/M0_DIR1") (class "Default")
      (node (ref "U17") (pin "30") (pinfunction "PD5_30") (pintype "bidirectional"))
      (node (ref "U9") (pin "P$11") (pinfunction "IN2_P$11") (pintype "bidirectional"))
    )
    (net (code "69") (name "/M0_EN") (class "Default")
      (node (ref "U17") (pin "14") (pinfunction "PB4(OC0A)_14") (pintype "bidirectional"))
      (node (ref "U9") (pin "P$10") (pinfunction "EN1_P$10") (pintype "bidirectional"))
      (node (ref "U9") (pin "P$12") (pinfunction "EN2_P$12") (pintype "bidirectional"))
    )
    (net (code "70") (name "/M1_DIR0") (class "Default")
      (node (ref "U10") (pin "P$9") (pinfunction "IN1_P$9") (pintype "bidirectional"))
      (node (ref "U17") (pin "31") (pinfunction "PD6_31") (pintype "bidirectional"))
    )
    (net (code "71") (name "/M1_DIR1") (class "Default")
      (node (ref "U10") (pin "P$11") (pinfunction "IN2_P$11") (pintype "bidirectional"))
      (node (ref "U17") (pin "32") (pinfunction "PD7_32") (pintype "bidirectional"))
    )
    (net (code "72") (name "/M1_EN") (class "Default")
      (node (ref "U10") (pin "P$10") (pinfunction "EN1_P$10") (pintype "bidirectional"))
      (node (ref "U10") (pin "P$12") (pinfunction "EN2_P$12") (pintype "bidirectional"))
      (node (ref "U17") (pin "17") (pinfunction "PB7(OC2A)_17") (pintype "bidirectional"))
    )
    (net (code "73") (name "/MISO") (class "Default")
      (node (ref "D5") (pin "3") (pinfunction "C_3") (pintype "passive"))
      (node (ref "R5") (pin "1") (pinfunction "1_1") (pintype "passive"))
      (node (ref "U17") (pin "13") (pinfunction "PB3(MISO)_13") (pintype "bidirectional"))
    )
    (net (code "74") (name "/MOSI") (class "Default")
      (node (ref "D4") (pin "3") (pinfunction "C_3") (pintype "passive"))
      (node (ref "R4") (pin "1") (pinfunction "1_1") (pintype "passive"))
      (node (ref "U17") (pin "12") (pinfunction "PB2(MOSI)_12") (pintype "bidirectional"))
    )
    (net (code "75") (name "/PWR_GATE") (class "Default")
      (node (ref "Q1") (pin "3") (pinfunction "D_3") (pintype "bidirectional"))
      (node (ref "R32") (pin "2") (pinfunction "2_2") (pintype "passive"))
      (node (ref "U$6") (pin "G1") (pinfunction "G1_G1") (pintype "bidirectional"))
      (node (ref "U$6") (pin "G2") (pinfunction "G2_G2") (pintype "bidirectional"))
    )
    (net (code "76") (name "/PWR_SW") (class "Default")
      (node (ref "Q2") (pin "2") (pinfunction "S_2") (pintype "bidirectional"))
      (node (ref "R44") (pin "1") (pinfunction "1_1") (pintype "passive"))
      (node (ref "U$6") (pin "S2") (pinfunction "S2_S2") (pintype "bidirectional"))
      (node (ref "U$7") (pin "S2") (pinfunction "S2_S2") (pintype "bidirectional"))
    )
    (net (code "77") (name "/RESET") (class "Default")
      (node (ref "C4") (pin "2") (pinfunction "2_2") (pintype "passive"))
      (node (ref "R39") (pin "1") (pinfunction "1_1") (pintype "passive"))
      (node (ref "R40") (pin "2") (pinfunction "2_2") (pintype "passive"))
      (node (ref "R56") (pin "1") (pinfunction "1_1") (pintype "passive"))
      (node (ref "RESET") (pin "3") (pinfunction "3_3") (pintype "passive"))
      (node (ref "RESET") (pin "4") (pinfunction "4_4") (pintype "passive"))
      (node (ref "U17") (pin "20") (pinfunction "RESET/PG5_20") (pintype "bidirectional"))
    )
    (net (code "78") (name "/RS") (class "Default")
      (node (ref "R33") (pin "1") (pinfunction "1_1") (pintype "passive"))
      (node (ref "U17") (pin "54") (pinfunction "PF7(ADC7)_54") (pintype "bidirectional"))
    )
    (net (code "79") (name "/RX") (class "Default")
      (node (ref "U1") (pin "1") (pinfunction "TXD_1") (pintype "output"))
      (node (ref "U17") (pin "28") (pinfunction "PD3_28") (pintype "bidirectional"))
    )
    (net (code "80") (name "/SCK") (class "Default")
      (node (ref "D6") (pin "3") (pinfunction "C_3") (pintype "passive"))
      (node (ref "R6") (pin "1") (pinfunction "1_1") (pintype "passive"))
      (node (ref "U17") (pin "11") (pinfunction "PB1(SCK)_11") (pintype "bidirectional"))
    )
    (net (code "81") (name "/SCL0") (class "Default")
      (node (ref "JP2") (pin "9") (pinfunction "9_9") (pintype "passive"))
      (node (ref "R7") (pin "2") (pinfunction "2_2") (pintype "passive"))
    )
    (net (code "82") (name "/SCL_5V") (class "Default")
      (node (ref "R60") (pin "1") (pinfunction "1_1") (pintype "passive"))
      (node (ref "U$10") (pin "3") (pinfunction "D_3") (pintype "bidirectional"))
      (node (ref "U17") (pin "6") (pinfunction "PE4(SCL)_6") (pintype "bidirectional"))
    )
    (net (code "83") (name "/SCL_IN") (class "Default")
      (node (ref "D7") (pin "3") (pinfunction "C_3") (pintype "passive"))
      (node (ref "R38") (pin "1") (pinfunction "1_1") (pintype "passive"))
      (node (ref "R7") (pin "1") (pinfunction "1_1") (pintype "passive"))
      (node (ref "U$10") (pin "2") (pinfunction "S_2") (pintype "bidirectional"))
      (node (ref "U$8") (pin "P$4") (pinfunction "SCL_P$4") (pintype "bidirectional"))
    )
    (net (code "84") (name "/SDA0") (class "Default")
      (node (ref "JP2") (pin "10") (pinfunction "10_10") (pintype "passive"))
      (node (ref "R8") (pin "2") (pinfunction "2_2") (pintype "passive"))
    )
    (net (code "85") (name "/SDA_5V") (class "Default")
      (node (ref "R58") (pin "1") (pinfunction "1_1") (pintype "passive"))
      (node (ref "U$9") (pin "3") (pinfunction "D_3") (pintype "bidirectional"))
      (node (ref "U17") (pin "7") (pinfunction "PE5(SDA)_7") (pintype "bidirectional"))
    )
    (net (code "86") (name "/SDA_IN") (class "Default")
      (node (ref "D8") (pin "3") (pinfunction "C_3") (pintype "passive"))
      (node (ref "R37") (pin "1") (pinfunction "1_1") (pintype "passive"))
      (node (ref "R8") (pin "1") (pinfunction "1_1") (pintype "passive"))
      (node (ref "U$8") (pin "P$6") (pinfunction "SDA_P$6") (pintype "bidirectional"))
      (node (ref "U$9") (pin "2") (pinfunction "S_2") (pintype "bidirectional"))
    )
    (net (code "87") (name "/SERVO0") (class "Default")
      (node (ref "JP3") (pin "1") (pinfunction "1_1") (pintype "passive"))
      (node (ref "R47") (pin "2") (pinfunction "2_2") (pintype "passive"))
    )
    (net (code "88") (name "/SERVO0_IN") (class "Default")
      (node (ref "D26") (pin "3") (pinfunction "C_3") (pintype "passive"))
      (node (ref "R47") (pin "1") (pinfunction "1_1") (pintype "passive"))
      (node (ref "U17") (pin "35") (pinfunction "PC0_35") (pintype "bidirectional"))
    )
    (net (code "89") (name "/SERVO1") (class "Default")
      (node (ref "JP3") (pin "2") (pinfunction "2_2") (pintype "passive"))
      (node (ref "R48") (pin "2") (pinfunction "2_2") (pintype "passive"))
    )
    (net (code "90") (name "/SERVO1_IN") (class "Default")
      (node (ref "D27") (pin "3") (pinfunction "C_3") (pintype "passive"))
      (node (ref "R48") (pin "1") (pinfunction "1_1") (pintype "passive"))
      (node (ref "U17") (pin "36") (pinfunction "PC1_36") (pintype "bidirectional"))
    )
    (net (code "91") (name "/SERVO2") (class "Default")
      (node (ref "JP3") (pin "3") (pinfunction "3_3") (pintype "passive"))
      (node (ref "R49") (pin "2") (pinfunction "2_2") (pintype "passive"))
    )
    (net (code "92") (name "/SERVO2_IN") (class "Default")
      (node (ref "D28") (pin "3") (pinfunction "C_3") (pintype "passive"))
      (node (ref "R49") (pin "1") (pinfunction "1_1") (pintype "passive"))
      (node (ref "U17") (pin "37") (pinfunction "PC2_37") (pintype "bidirectional"))
    )
    (net (code "93") (name "/SERVO3") (class "Default")
      (node (ref "JP3") (pin "4") (pinfunction "4_4") (pintype "passive"))
      (node (ref "R50") (pin "2") (pinfunction "2_2") (pintype "passive"))
    )
    (net (code "94") (name "/SERVO3_IN") (class "Default")
      (node (ref "D29") (pin "3") (pinfunction "C_3") (pintype "passive"))
      (node (ref "R50") (pin "1") (pinfunction "1_1") (pintype "passive"))
      (node (ref "U17") (pin "38") (pinfunction "PC3_38") (pintype "bidirectional"))
    )
    (net (code "95") (name "/SS") (class "Default")
      (node (ref "D3") (pin "3") (pinfunction "C_3") (pintype "passive"))
      (node (ref "R3") (pin "1") (pinfunction "1_1") (pintype "passive"))
      (node (ref "U17") (pin "10") (pinfunction "PB0(SS)_10") (pintype "bidirectional"))
    )
    (net (code "96") (name "/SW1") (class "Default")
      (node (ref "S2") (pin "3") (pinfunction "3_3") (pintype "passive"))
      (node (ref "S2") (pin "4") (pinfunction "4_4") (pintype "passive"))
      (node (ref "U17") (pin "9") (pinfunction "PE7_9") (pintype "bidirectional"))
    )
    (net (code "97") (name "/TX") (class "Default")
      (node (ref "U1") (pin "5") (pinfunction "RXD_5") (pintype "input"))
      (node (ref "U17") (pin "27") (pinfunction "PD2_27") (pintype "bidirectional"))
    )
    (net (code "98") (name "/USBGATE") (class "Default")
      (node (ref "Q1") (pin "1") (pinfunction "G_1") (pintype "bidirectional"))
      (node (ref "R42") (pin "1") (pinfunction "1_1") (pintype "passive"))
      (node (ref "U$7") (pin "G1") (pinfunction "G1_G1") (pintype "bidirectional"))
      (node (ref "U$7") (pin "G2") (pinfunction "G2_G2") (pintype "bidirectional"))
      (node (ref "U16") (pin "1") (pinfunction "OUT_1") (pintype "output"))
    )
    (net (code "99") (name "/USB_5V") (class "Default")
      (node (ref "D24") (pin "2") (pinfunction "A2_2") (pintype "passive"))
      (node (ref "F2") (pin "2") (pinfunction "2_2") (pintype "passive"))
      (node (ref "R54") (pin "2") (pinfunction "2_2") (pintype "passive"))
      (node (ref "R55") (pin "1") (pinfunction "1_1") (pintype "passive"))
      (node (ref "U$7") (pin "S1") (pinfunction "S1_S1") (pintype "bidirectional"))
      (node (ref "U1") (pin "20") (pinfunction "VCC_20") (pintype "power_in"))
      (node (ref "U1") (pin "4") (pinfunction "VCCIO_4") (pintype "power_in"))
      (node (ref "U16") (pin "8") (pinfunction "V+_8") (pintype "power_in"))
    )
    (net (code "100") (name "/VIN") (class "Default")
      (node (ref "F1") (pin "1") (pinfunction "1_1") (pintype "passive"))
      (node (ref "J1") (pin "PWR") (pinfunction "PWR_PWR") (pintype "bidirectional"))
      (node (ref "R35") (pin "2") (pinfunction "2_2") (pintype "passive"))
    )
    (net (code "101") (name "/VIN1") (class "Default")
      (node (ref "D24") (pin "1") (pinfunction "A1_1") (pintype "passive"))
      (node (ref "F1") (pin "2") (pinfunction "2_2") (pintype "passive"))
      (node (ref "U$6") (pin "S1") (pinfunction "S1_S1") (pintype "bidirectional"))
    )
    (net (code "102") (name "/VIN_F") (class "Default")
      (node (ref "C13") (pin "1") (pinfunction "1_1") (pintype "passive"))
      (node (ref "JP4") (pin "8") (pinfunction "8_8") (pintype "passive"))
      (node (ref "JP6") (pin "1") (pinfunction "1_1") (pintype "passive"))
      (node (ref "JP6") (pin "2") (pinfunction "2_2") (pintype "passive"))
      (node (ref "JP6") (pin "3") (pinfunction "3_3") (pintype "passive"))
      (node (ref "JP6") (pin "4") (pinfunction "4_4") (pintype "passive"))
      (node (ref "Q2") (pin "3") (pinfunction "D_3") (pintype "bidirectional"))
      (node (ref "R45") (pin "2") (pinfunction "2_2") (pintype "passive"))
      (node (ref "U$3") (pin "P$2") (pinfunction "VIN_P$2") (pintype "bidirectional"))
      (node (ref "U$3") (pin "P$3") (pinfunction "EN_P$3") (pintype "bidirectional"))
      (node (ref "U10") (pin "P$1") (pinfunction "VM1_P$1") (pintype "bidirectional"))
      (node (ref "U10") (pin "P$2") (pinfunction "VM2_P$2") (pintype "bidirectional"))
      (node (ref "U9") (pin "P$1") (pinfunction "VM1_P$1") (pintype "bidirectional"))
      (node (ref "U9") (pin "P$2") (pinfunction "VM2_P$2") (pintype "bidirectional"))
    )
    (net (code "103") (name "/VREG_OUT") (class "Default")
      (node (ref "C11") (pin "1") (pinfunction "1_1") (pintype "passive"))
      (node (ref "C12") (pin "1") (pinfunction "1_1") (pintype "passive"))
      (node (ref "F3") (pin "1") (pinfunction "1_1") (pintype "passive"))
      (node (ref "U$3") (pin "P$8") (pinfunction "FB_P$8") (pintype "bidirectional"))
      (node (ref "U$3") (pin "P$9") (pinfunction "VOUT_P$9") (pintype "bidirectional"))
    )
    (net (code "104") (name "Net-(D23-PadA)") (class "Default")
      (node (ref "D23") (pin "A") (pinfunction "A_A") (pintype "passive"))
      (node (ref "R29") (pin "2") (pinfunction "2_2") (pintype "passive"))
    )
    (net (code "105") (name "Net-(D24-CC)") (class "Default")
      (node (ref "D24") (pin "3") (pinfunction "CC_3") (pintype "passive"))
      (node (ref "Q1") (pin "2") (pinfunction "S_2") (pintype "bidirectional"))
      (node (ref "R23") (pin "2") (pinfunction "2_2") (pintype "passive"))
      (node (ref "R42") (pin "2") (pinfunction "2_2") (pintype "passive"))
    )
    (net (code "106") (name "Net-(D25-PadC)") (class "Default")
      (node (ref "D25") (pin "C") (pinfunction "C_C") (pintype "passive"))
      (node (ref "R41") (pin "2") (pinfunction "2_2") (pintype "passive"))
    )
    (net (code "107") (name "Net-(D30-PadC)") (class "Default")
      (node (ref "D30") (pin "C") (pinfunction "C_C") (pintype "passive"))
      (node (ref "R51") (pin "2") (pinfunction "2_2") (pintype "passive"))
    )
    (net (code "108") (name "Net-(D31-PadC)") (class "Default")
      (node (ref "D31") (pin "C") (pinfunction "C_C") (pintype "passive"))
      (node (ref "R52") (pin "2") (pinfunction "2_2") (pintype "passive"))
    )
    (net (code "109") (name "Net-(D34-PadA)") (class "Default")
      (node (ref "D34") (pin "A") (pinfunction "A_A") (pintype "passive"))
      (node (ref "R57") (pin "2") (pinfunction "2_2") (pintype "passive"))
    )
    (net (code "110") (name "Net-(F2-Pad1)") (class "Default")
      (node (ref "F2") (pin "1") (pinfunction "1_1") (pintype "passive"))
      (node (ref "JP9") (pin "VBUS") (pinfunction "VBUS_VBUS") (pintype "bidirectional"))
    )
    (net (code "111") (name "Net-(JP4-Pad3)") (class "Default")
      (node (ref "JP4") (pin "3") (pinfunction "3_3") (pintype "passive"))
      (node (ref "R56") (pin "2") (pinfunction "2_2") (pintype "passive"))
    )
    (net (code "112") (name "Net-(JP8-Pad5)") (class "Default")
      (node (ref "JP8") (pin "5") (pinfunction "5_5") (pintype "bidirectional"))
      (node (ref "R39") (pin "2") (pinfunction "2_2") (pintype "passive"))
    )
    (net (code "113") (name "Net-(POWER-PadP$1)") (class "Default")
      (node (ref "POWER") (pin "P$1") (pinfunction "P$1_P$1") (pintype "bidirectional"))
      (node (ref "R43") (pin "2") (pinfunction "2_2") (pintype "passive"))
    )
    (net (code "114") (name "Net-(Q2-G)") (class "Default")
      (node (ref "Q2") (pin "1") (pinfunction "G_1") (pintype "bidirectional"))
      (node (ref "R43") (pin "1") (pinfunction "1_1") (pintype "passive"))
      (node (ref "R44") (pin "2") (pinfunction "2_2") (pintype "passive"))
    )
    (net (code "115") (name "Net-(Q3-G)") (class "Default")
      (node (ref "Q3") (pin "1") (pinfunction "G_1") (pintype "bidirectional"))
      (node (ref "R25") (pin "1") (pinfunction "1_1") (pintype "passive"))
      (node (ref "U12") (pin "7") (pinfunction "OUT_7") (pintype "output"))
    )
    (net (code "116") (name "Net-(Q4-G)") (class "Default")
      (node (ref "Q4") (pin "1") (pinfunction "G_1") (pintype "bidirectional"))
      (node (ref "R30") (pin "1") (pinfunction "1_1") (pintype "passive"))
      (node (ref "U12") (pin "1") (pinfunction "OUT_1") (pintype "output"))
    )
    (net (code "117") (name "Net-(U$1-P$3)") (class "Default")
      (node (ref "U$1") (pin "3") (pinfunction "P$3_3") (pintype "bidirectional"))
      (node (ref "U$2") (pin "2") (pinfunction "S_2") (pintype "passive"))
    )
    (net (code "118") (name "Net-(U$1-P$4)") (class "Default")
      (node (ref "R33") (pin "2") (pinfunction "2_2") (pintype "passive"))
      (node (ref "U$1") (pin "4") (pinfunction "P$4_4") (pintype "bidirectional"))
    )
    (net (code "119") (name "Net-(U$1-P$7)") (class "Default")
      (node (ref "R34") (pin "1") (pinfunction "1_1") (pintype "passive"))
      (node (ref "U$1") (pin "7") (pinfunction "P$7_7") (pintype "bidirectional"))
    )
    (net (code "120") (name "Net-(U$3-L1)") (class "Default")
      (node (ref "U$3") (pin "P$1") (pinfunction "L1_P$1") (pintype "bidirectional"))
      (node (ref "U$4") (pin "P$1") (pinfunction "1_P$1") (pintype "passive"))
    )
    (net (code "121") (name "Net-(U$3-L2)") (class "Default")
      (node (ref "U$3") (pin "P$10") (pinfunction "L2_P$10") (pintype "bidirectional"))
      (node (ref "U$4") (pin "P$2") (pinfunction "2_P$2") (pintype "passive"))
    )
    (net (code "122") (name "Net-(U$3-PG)") (class "Default")
      (node (ref "R28") (pin "2") (pinfunction "2_2") (pintype "passive"))
      (node (ref "U$3") (pin "P$5") (pinfunction "PG_P$5") (pintype "bidirectional"))
    )
    (net (code "123") (name "Net-(U$3-VAUX)") (class "Default")
      (node (ref "C10") (pin "1") (pinfunction "1_1") (pintype "passive"))
      (node (ref "U$3") (pin "P$6") (pinfunction "VAUX_P$6") (pintype "bidirectional"))
    )
    (net (code "124") (name "Net-(U$6-D1-PadD1@1)") (class "Default")
      (node (ref "U$6") (pin "D1@1") (pinfunction "D1_D1@1") (pintype "bidirectional"))
      (node (ref "U$6") (pin "D1@2") (pinfunction "D1_D1@2") (pintype "bidirectional"))
      (node (ref "U$6") (pin "D2@1") (pinfunction "D2_D2@1") (pintype "bidirectional"))
      (node (ref "U$6") (pin "D2@2") (pinfunction "D2_D2@2") (pintype "bidirectional"))
    )
    (net (code "125") (name "Net-(U$7-D1-PadD1@1)") (class "Default")
      (node (ref "U$7") (pin "D1@1") (pinfunction "D1_D1@1") (pintype "bidirectional"))
      (node (ref "U$7") (pin "D1@2") (pinfunction "D1_D1@2") (pintype "bidirectional"))
      (node (ref "U$7") (pin "D2@1") (pinfunction "D2_D2@1") (pintype "bidirectional"))
      (node (ref "U$7") (pin "D2@2") (pinfunction "D2_D2@2") (pintype "bidirectional"))
    )
    (net (code "126") (name "Net-(U$8-BYP)") (class "Default")
      (node (ref "C5") (pin "1") (pinfunction "1_1") (pintype "passive"))
      (node (ref "U$8") (pin "P$2") (pinfunction "BYP_P$2") (pintype "bidirectional"))
    )
    (net (code "127") (name "Net-(U1-DTR)") (class "Default")
      (node (ref "R63") (pin "2") (pinfunction "2_2") (pintype "passive"))
      (node (ref "U1") (pin "2") (pinfunction "DTR_2") (pintype "bidirectional"))
    )
    (net (code "128") (name "Net-(U1-RXLED)") (class "Default")
      (node (ref "D34") (pin "C") (pinfunction "C_C") (pintype "passive"))
      (node (ref "U1") (pin "22") (pinfunction "RXLED_22") (pintype "bidirectional"))
    )
    (net (code "129") (name "Net-(U1-TXLED)") (class "Default")
      (node (ref "D23") (pin "C") (pinfunction "C_C") (pintype "passive"))
      (node (ref "U1") (pin "23") (pinfunction "TXLED_23") (pintype "bidirectional"))
    )
    (net (code "130") (name "Net-(U1-USBDM)") (class "Default")
      (node (ref "JP9") (pin "D-") (pinfunction "D-_D-") (pintype "bidirectional"))
      (node (ref "U1") (pin "16") (pinfunction "USBDM_16") (pintype "bidirectional"))
    )
    (net (code "131") (name "Net-(U1-USBDP)") (class "Default")
      (node (ref "JP9") (pin "D+") (pinfunction "D+_D+") (pintype "bidirectional"))
      (node (ref "U1") (pin "15") (pinfunction "USBDP_15") (pintype "bidirectional"))
    )
    (net (code "132") (name "Net-(U4-RX)") (class "Default")
      (node (ref "R61") (pin "1") (pinfunction "1_1") (pintype "passive"))
      (node (ref "R62") (pin "2") (pinfunction "2_2") (pintype "passive"))
      (node (ref "U4") (pin "2") (pinfunction "RX_2") (pintype "bidirectional"))
    )
    (net (code "133") (name "Net-(U8-EN)") (class "Default")
      (node (ref "R65") (pin "1") (pinfunction "1_1") (pintype "passive"))
      (node (ref "U8") (pin "P$3") (pinfunction "EN_P$3") (pintype "bidirectional"))
    )
    (net (code "134") (name "Net-(U8-ILIM)") (class "Default")
      (node (ref "R53") (pin "2") (pinfunction "2_2") (pintype "passive"))
      (node (ref "U8") (pin "P$5") (pinfunction "ILIM_P$5") (pintype "bidirectional"))
    )
    (net (code "135") (name "Net-(U12A-+IN)") (class "Default")
      (node (ref "R27") (pin "1") (pinfunction "1_1") (pintype "passive"))
      (node (ref "R31") (pin "2") (pinfunction "2_2") (pintype "passive"))
      (node (ref "U12") (pin "3") (pinfunction "+IN_3") (pintype "input"))
    )
    (net (code "136") (name "Net-(U12B-+IN)") (class "Default")
      (node (ref "R24") (pin "1") (pinfunction "1_1") (pintype "passive"))
      (node (ref "R26") (pin "2") (pinfunction "2_2") (pintype "passive"))
      (node (ref "U12") (pin "5") (pinfunction "+IN_5") (pintype "input"))
    )
    (net (code "137") (name "Net-(U16A-+IN)") (class "Default")
      (node (ref "R35") (pin "1") (pinfunction "1_1") (pintype "passive"))
      (node (ref "R36") (pin "2") (pinfunction "2_2") (pintype "passive"))
      (node (ref "U16") (pin "3") (pinfunction "+IN_3") (pintype "input"))
    )
    (net (code "138") (name "Net-(U17-PF6(ADC6))") (class "Default")
      (node (ref "R45") (pin "1") (pinfunction "1_1") (pintype "passive"))
      (node (ref "R46") (pin "2") (pinfunction "2_2") (pintype "passive"))
      (node (ref "U17") (pin "55") (pinfunction "PF6(ADC6)_55") (pintype "bidirectional"))
    )
    (net (code "139") (name "Net-(U17-PG2)") (class "Default")
      (node (ref "R55") (pin "2") (pinfunction "2_2") (pintype "passive"))
      (node (ref "U17") (pin "43") (pinfunction "PG2_43") (pintype "bidirectional"))
    )
    (net (code "140") (name "Net-(U17-XTAL1)") (class "Default")
      (node (ref "C1") (pin "2") (pinfunction "2_2") (pintype "passive"))
      (node (ref "U17") (pin "24") (pinfunction "XTAL1_24") (pintype "bidirectional"))
      (node (ref "Y1") (pin "P$1") (pinfunction "1_P$1") (pintype "passive"))
    )
    (net (code "141") (name "Net-(U17-XTAL2)") (class "Default")
      (node (ref "C2") (pin "2") (pinfunction "2_2") (pintype "passive"))
      (node (ref "U17") (pin "23") (pinfunction "XTAL2_23") (pintype "bidirectional"))
      (node (ref "Y1") (pin "P$2") (pinfunction "2_P$2") (pintype "passive"))
    )
    (net (code "142") (name "unconnected-(JP4-Pad1)") (class "Default")
      (node (ref "JP4") (pin "1") (pinfunction "1_1") (pintype "passive"))
    )
    (net (code "143") (name "unconnected-(JP12-Pad1)") (class "Default")
      (node (ref "JP12") (pin "1") (pinfunction "1_1") (pintype "passive"))
    )
    (net (code "144") (name "unconnected-(JP12-Pad2)") (class "Default")
      (node (ref "JP12") (pin "2") (pinfunction "2_2") (pintype "passive"))
    )
    (net (code "145") (name "unconnected-(U$8-INT2-PadP$9)") (class "Default")
      (node (ref "U$8") (pin "P$9") (pinfunction "INT2_P$9") (pintype "bidirectional"))
    )
    (net (code "146") (name "unconnected-(U$8-NC1-PadP$3)") (class "Default")
      (node (ref "U$8") (pin "P$3") (pinfunction "NC1_P$3") (pintype "bidirectional"))
    )
    (net (code "147") (name "unconnected-(U1-3V3OUT-Pad17)") (class "Default")
      (node (ref "U1") (pin "17") (pinfunction "3V3OUT_17") (pintype "output"))
    )
    (net (code "148") (name "unconnected-(U1-CTS-Pad11)") (class "Default")
      (node (ref "U1") (pin "11") (pinfunction "CTS_11") (pintype "bidirectional"))
    )
    (net (code "149") (name "unconnected-(U1-RTS-Pad3)") (class "Default")
      (node (ref "U1") (pin "3") (pinfunction "RTS_3") (pintype "bidirectional"))
    )
    (net (code "150") (name "unconnected-(U4-AIO0-Pad9)") (class "Default")
      (node (ref "U4") (pin "9") (pinfunction "AIO0_9") (pintype "bidirectional"))
    )
    (net (code "151") (name "unconnected-(U4-AIO1-Pad10)") (class "Default")
      (node (ref "U4") (pin "10") (pinfunction "AIO1_10") (pintype "bidirectional"))
    )
    (net (code "152") (name "unconnected-(U4-CLK-Pad19)") (class "Default")
      (node (ref "U4") (pin "19") (pinfunction "CLK_19") (pintype "bidirectional"))
    )
    (net (code "153") (name "unconnected-(U4-CSB-Pad16)") (class "Default")
      (node (ref "U4") (pin "16") (pinfunction "CSB_16") (pintype "bidirectional"))
    )
    (net (code "154") (name "unconnected-(U4-CTS-Pad3)") (class "Default")
      (node (ref "U4") (pin "3") (pinfunction "CTS_3") (pintype "bidirectional"))
    )
    (net (code "155") (name "unconnected-(U4-MISO-Pad18)") (class "Default")
      (node (ref "U4") (pin "18") (pinfunction "MISO_18") (pintype "bidirectional"))
    )
    (net (code "156") (name "unconnected-(U4-MOSI-Pad17)") (class "Default")
      (node (ref "U4") (pin "17") (pinfunction "MOSI_17") (pintype "bidirectional"))
    )
    (net (code "157") (name "unconnected-(U4-NC-Pad14)") (class "Default")
      (node (ref "U4") (pin "14") (pinfunction "NC_14") (pintype "bidirectional"))
    )
    (net (code "158") (name "unconnected-(U4-PCM_CLK-Pad5)") (class "Default")
      (node (ref "U4") (pin "5") (pinfunction "PCM_CLK_5") (pintype "bidirectional"))
    )
    (net (code "159") (name "unconnected-(U4-PCM_IN-Pad7)") (class "Default")
      (node (ref "U4") (pin "7") (pinfunction "PCM_IN_7") (pintype "bidirectional"))
    )
    (net (code "160") (name "unconnected-(U4-PCM_OUT-Pad6)") (class "Default")
      (node (ref "U4") (pin "6") (pinfunction "PCM_OUT_6") (pintype "bidirectional"))
    )
    (net (code "161") (name "unconnected-(U4-PCN_SYNC-Pad8)") (class "Default")
      (node (ref "U4") (pin "8") (pinfunction "PCN_SYNC_8") (pintype "bidirectional"))
    )
    (net (code "162") (name "unconnected-(U4-PIO0-Pad23)") (class "Default")
      (node (ref "U4") (pin "23") (pinfunction "PIO0_23") (pintype "bidirectional"))
    )
    (net (code "163") (name "unconnected-(U4-PIO1-Pad24)") (class "Default")
      (node (ref "U4") (pin "24") (pinfunction "PIO1_24") (pintype "bidirectional"))
    )
    (net (code "164") (name "unconnected-(U4-PIO2-Pad25)") (class "Default")
      (node (ref "U4") (pin "25") (pinfunction "PIO2_25") (pintype "bidirectional"))
    )
    (net (code "165") (name "unconnected-(U4-PIO3-Pad26)") (class "Default")
      (node (ref "U4") (pin "26") (pinfunction "PIO3_26") (pintype "bidirectional"))
    )
    (net (code "166") (name "unconnected-(U4-PIO4-Pad27)") (class "Default")
      (node (ref "U4") (pin "27") (pinfunction "PIO4_27") (pintype "bidirectional"))
    )
    (net (code "167") (name "unconnected-(U4-PIO5-Pad28)") (class "Default")
      (node (ref "U4") (pin "28") (pinfunction "PIO5_28") (pintype "bidirectional"))
    )
    (net (code "168") (name "unconnected-(U4-PIO6-Pad29)") (class "Default")
      (node (ref "U4") (pin "29") (pinfunction "PIO6_29") (pintype "bidirectional"))
    )
    (net (code "169") (name "unconnected-(U4-PIO7-Pad30)") (class "Default")
      (node (ref "U4") (pin "30") (pinfunction "PIO7_30") (pintype "bidirectional"))
    )
    (net (code "170") (name "unconnected-(U4-PIO8-Pad31)") (class "Default")
      (node (ref "U4") (pin "31") (pinfunction "PIO8_31") (pintype "bidirectional"))
    )
    (net (code "171") (name "unconnected-(U4-PIO9-Pad32)") (class "Default")
      (node (ref "U4") (pin "32") (pinfunction "PIO9_32") (pintype "bidirectional"))
    )
    (net (code "172") (name "unconnected-(U4-PIO10-Pad33)") (class "Default")
      (node (ref "U4") (pin "33") (pinfunction "PIO10_33") (pintype "bidirectional"))
    )
    (net (code "173") (name "unconnected-(U4-RST-Pad11)") (class "Default")
      (node (ref "U4") (pin "11") (pinfunction "RST_11") (pintype "bidirectional"))
    )
    (net (code "174") (name "unconnected-(U4-RTS-Pad4)") (class "Default")
      (node (ref "U4") (pin "4") (pinfunction "RTS_4") (pintype "bidirectional"))
    )
    (net (code "175") (name "unconnected-(U4-VBUSD+-Pad20)") (class "Default")
      (node (ref "U4") (pin "20") (pinfunction "VBUSD+_20") (pintype "bidirectional"))
    )
    (net (code "176") (name "unconnected-(U4-VBUSD--Pad15)") (class "Default")
      (node (ref "U4") (pin "15") (pinfunction "VBUSD-_15") (pintype "bidirectional"))
    )
    (net (code "177") (name "unconnected-(U7-NC-PadP$5)") (class "Default")
      (node (ref "U7") (pin "P$5") (pinfunction "NC_P$5") (pintype "bidirectional"))
    )
    (net (code "178") (name "unconnected-(U8-FAULT-PadP$4)") (class "Default")
      (node (ref "U8") (pin "P$4") (pinfunction "FAULT_P$4") (pintype "bidirectional"))
    )
    (net (code "179") (name "unconnected-(U16B-OUT-Pad7)") (class "Default")
      (node (ref "U16") (pin "7") (pinfunction "OUT_7") (pintype "output"))
    )
    (net (code "180") (name "unconnected-(U17-NC-Pad1)") (class "Default")
      (node (ref "U17") (pin "1") (pinfunction "NC_1") (pintype "bidirectional"))
    )
  )
)
